# tfp401_board.net
KiCad netlist of a schematic drawn in EAGLE
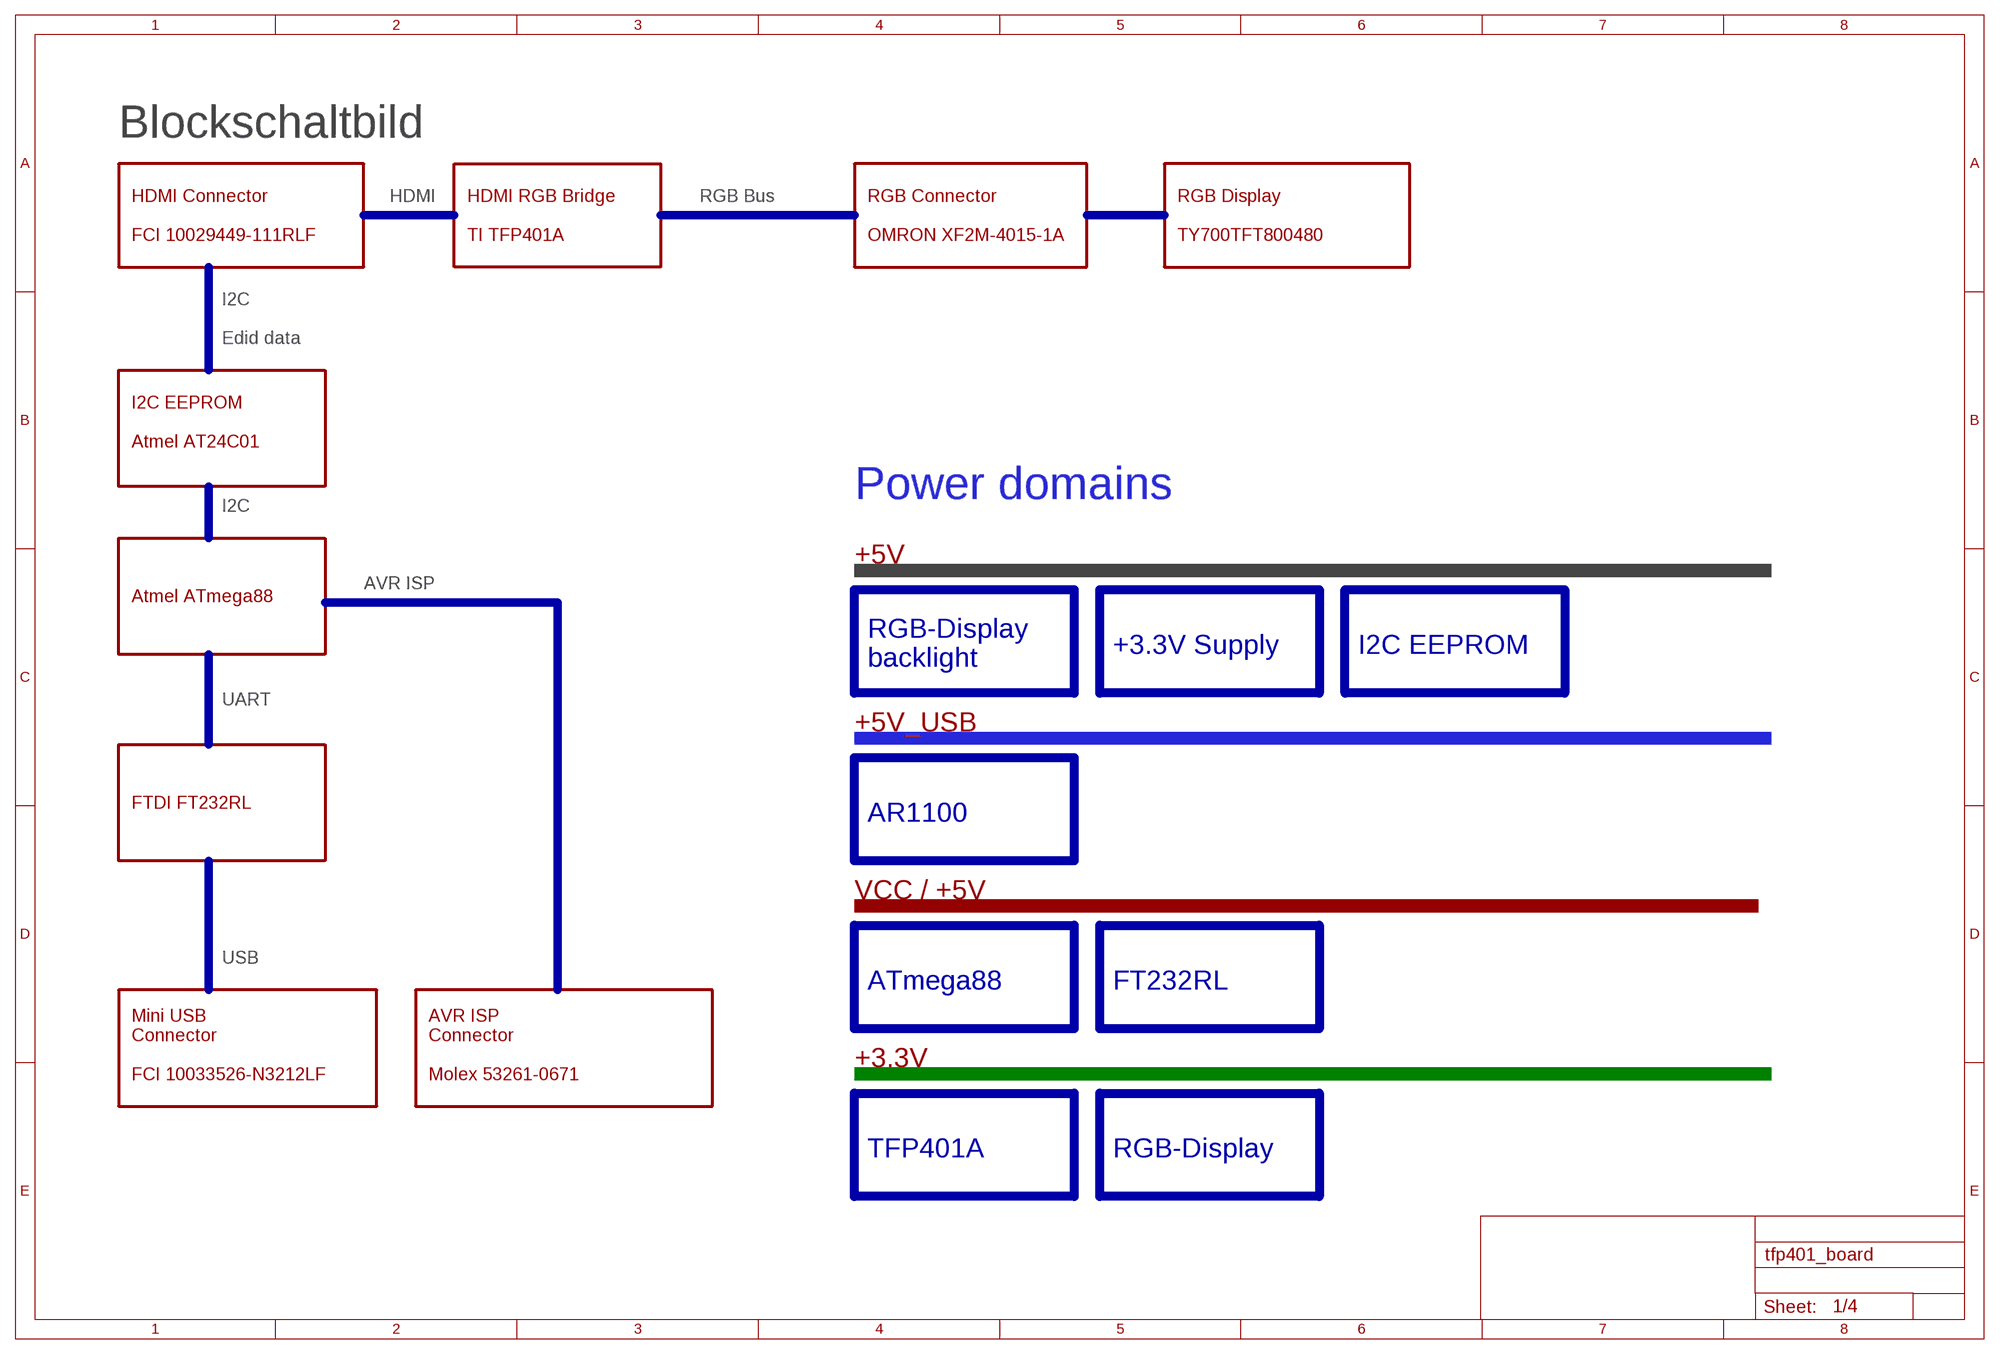
[diagram p0: schematic, sheet 1]
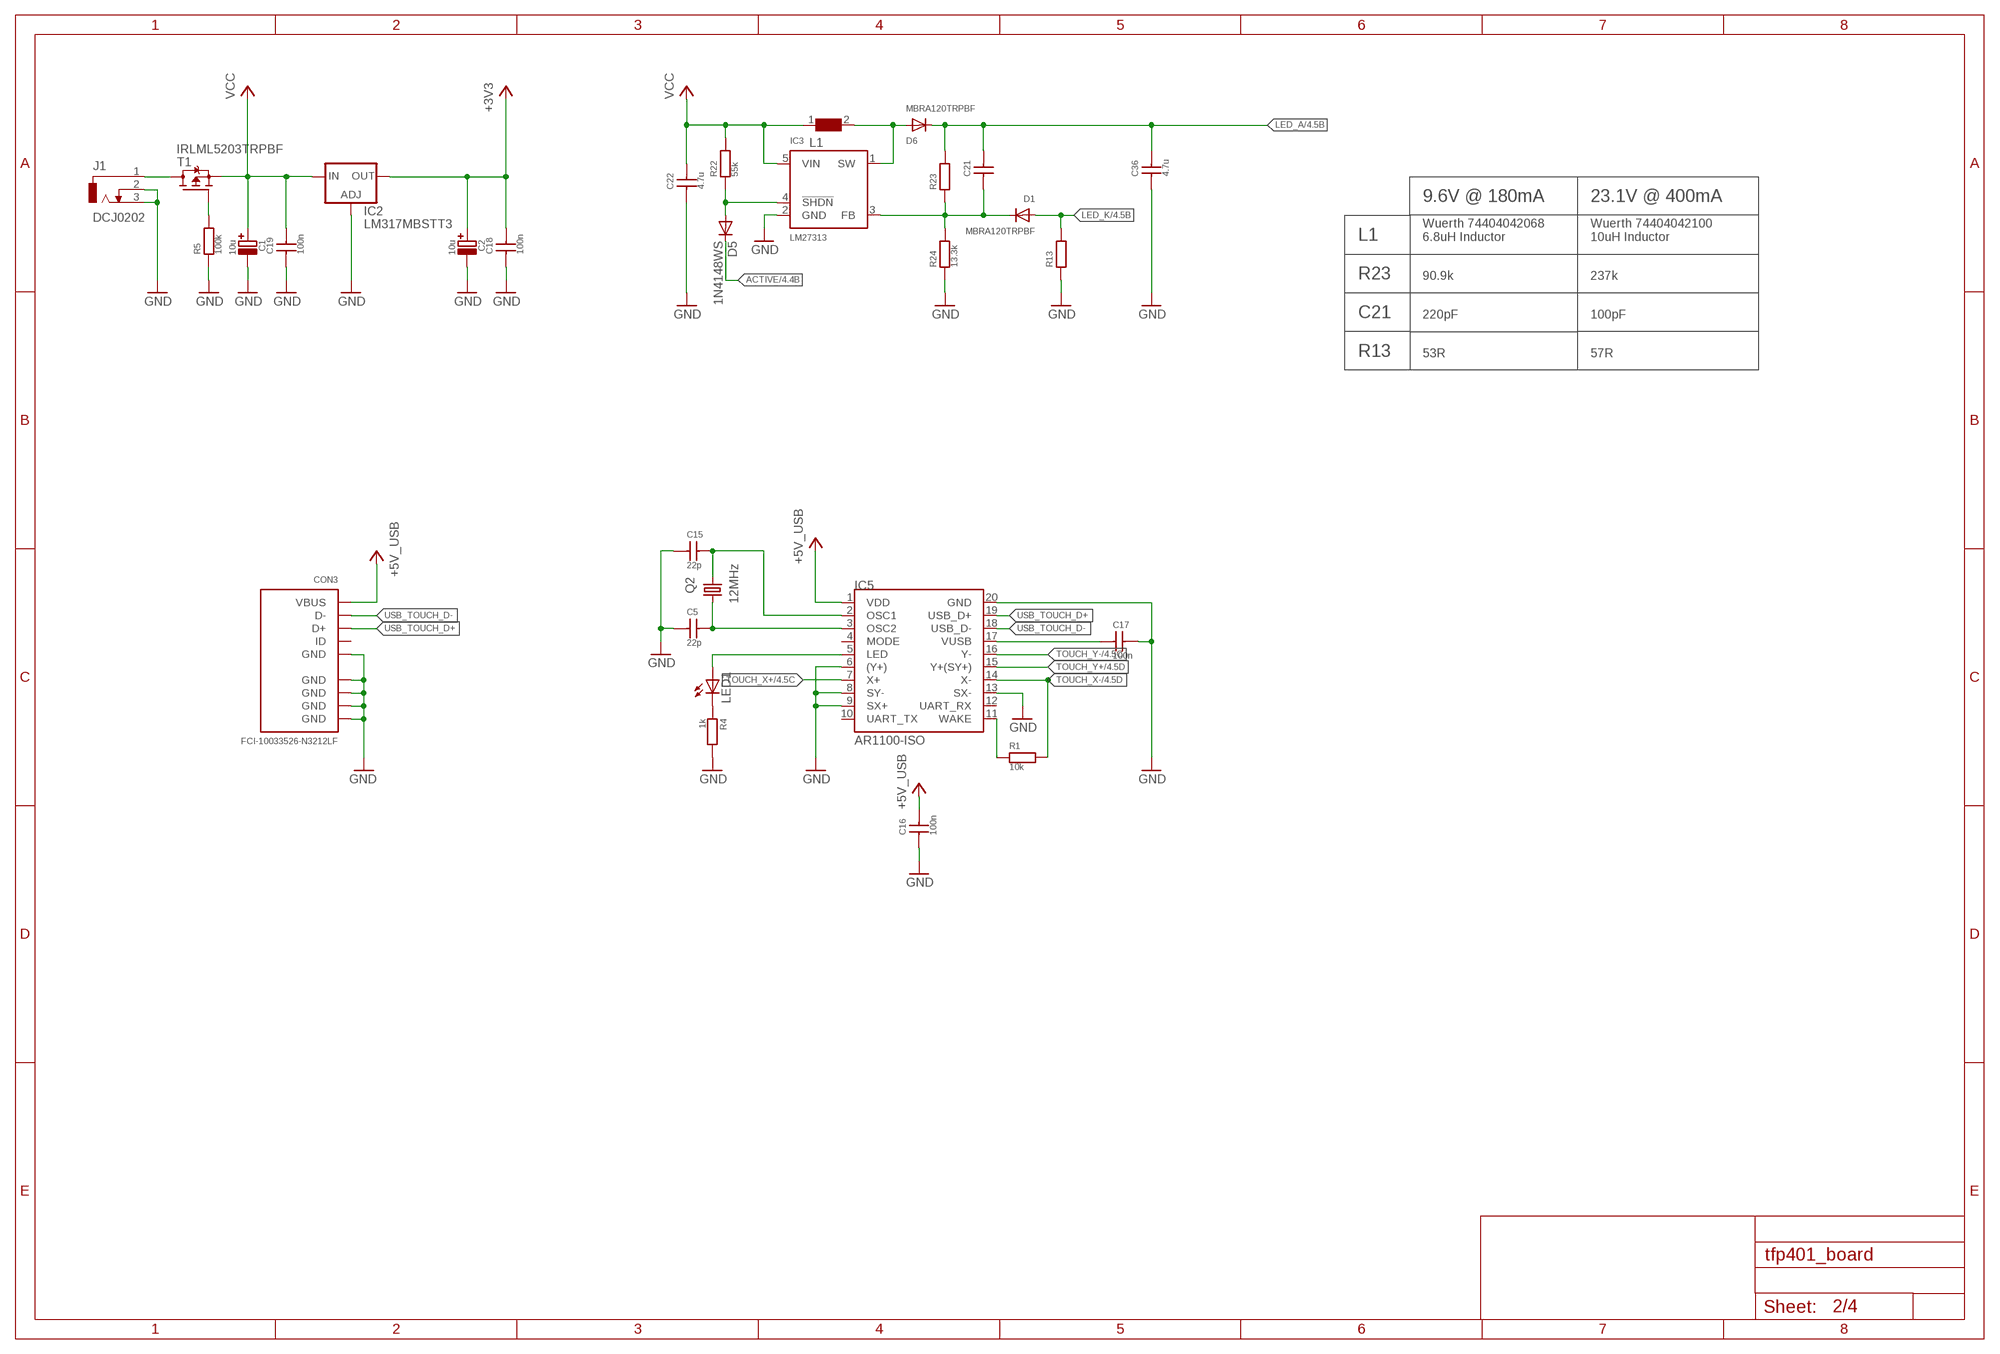
[diagram p1: schematic, sheet 2]
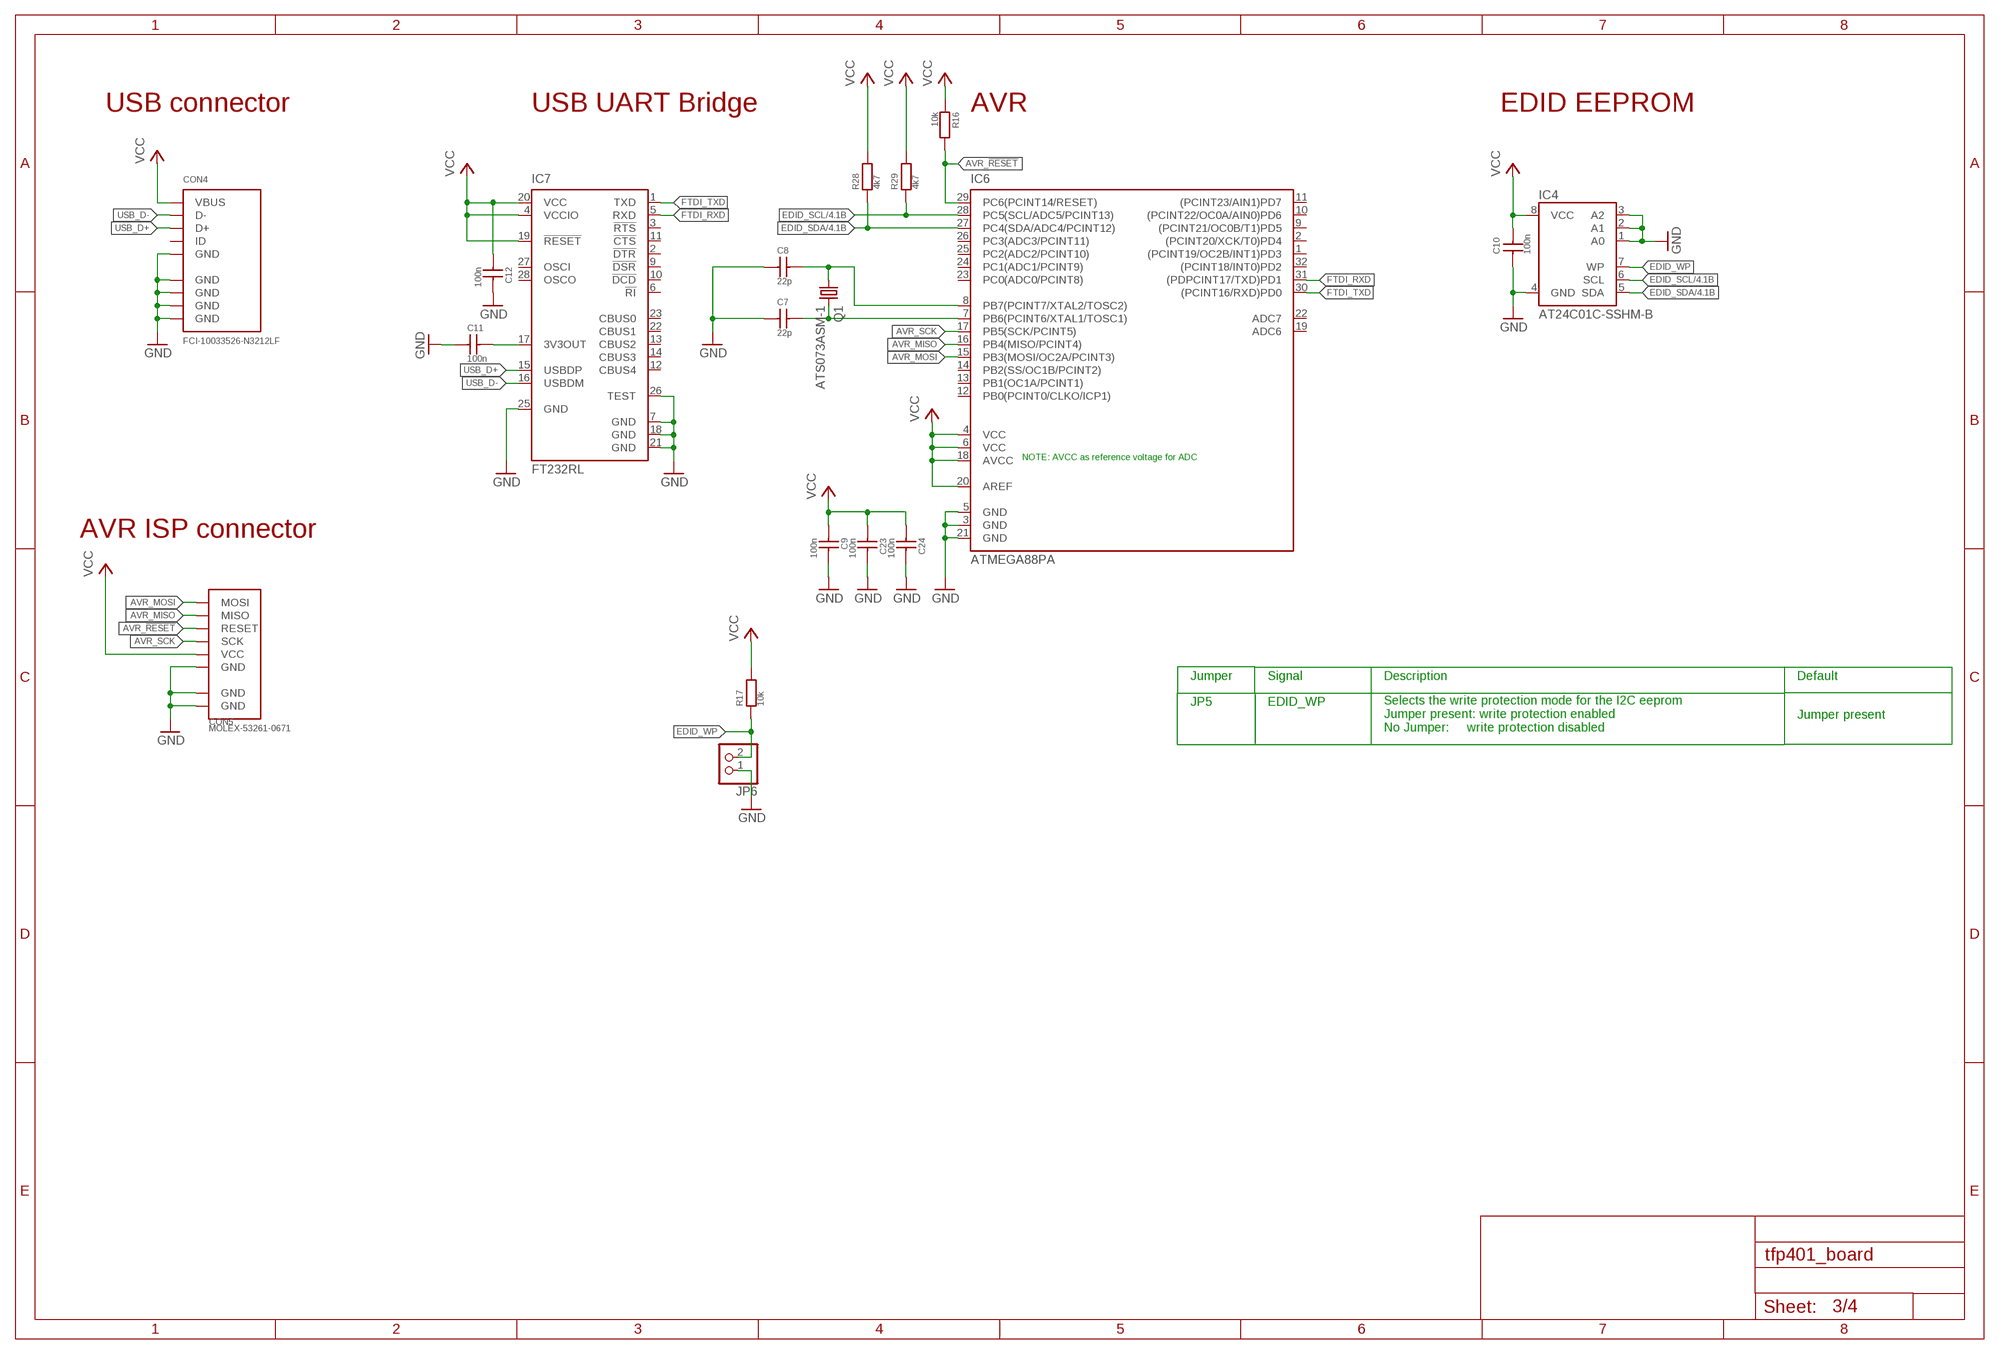
[diagram p2: schematic, sheet 3]
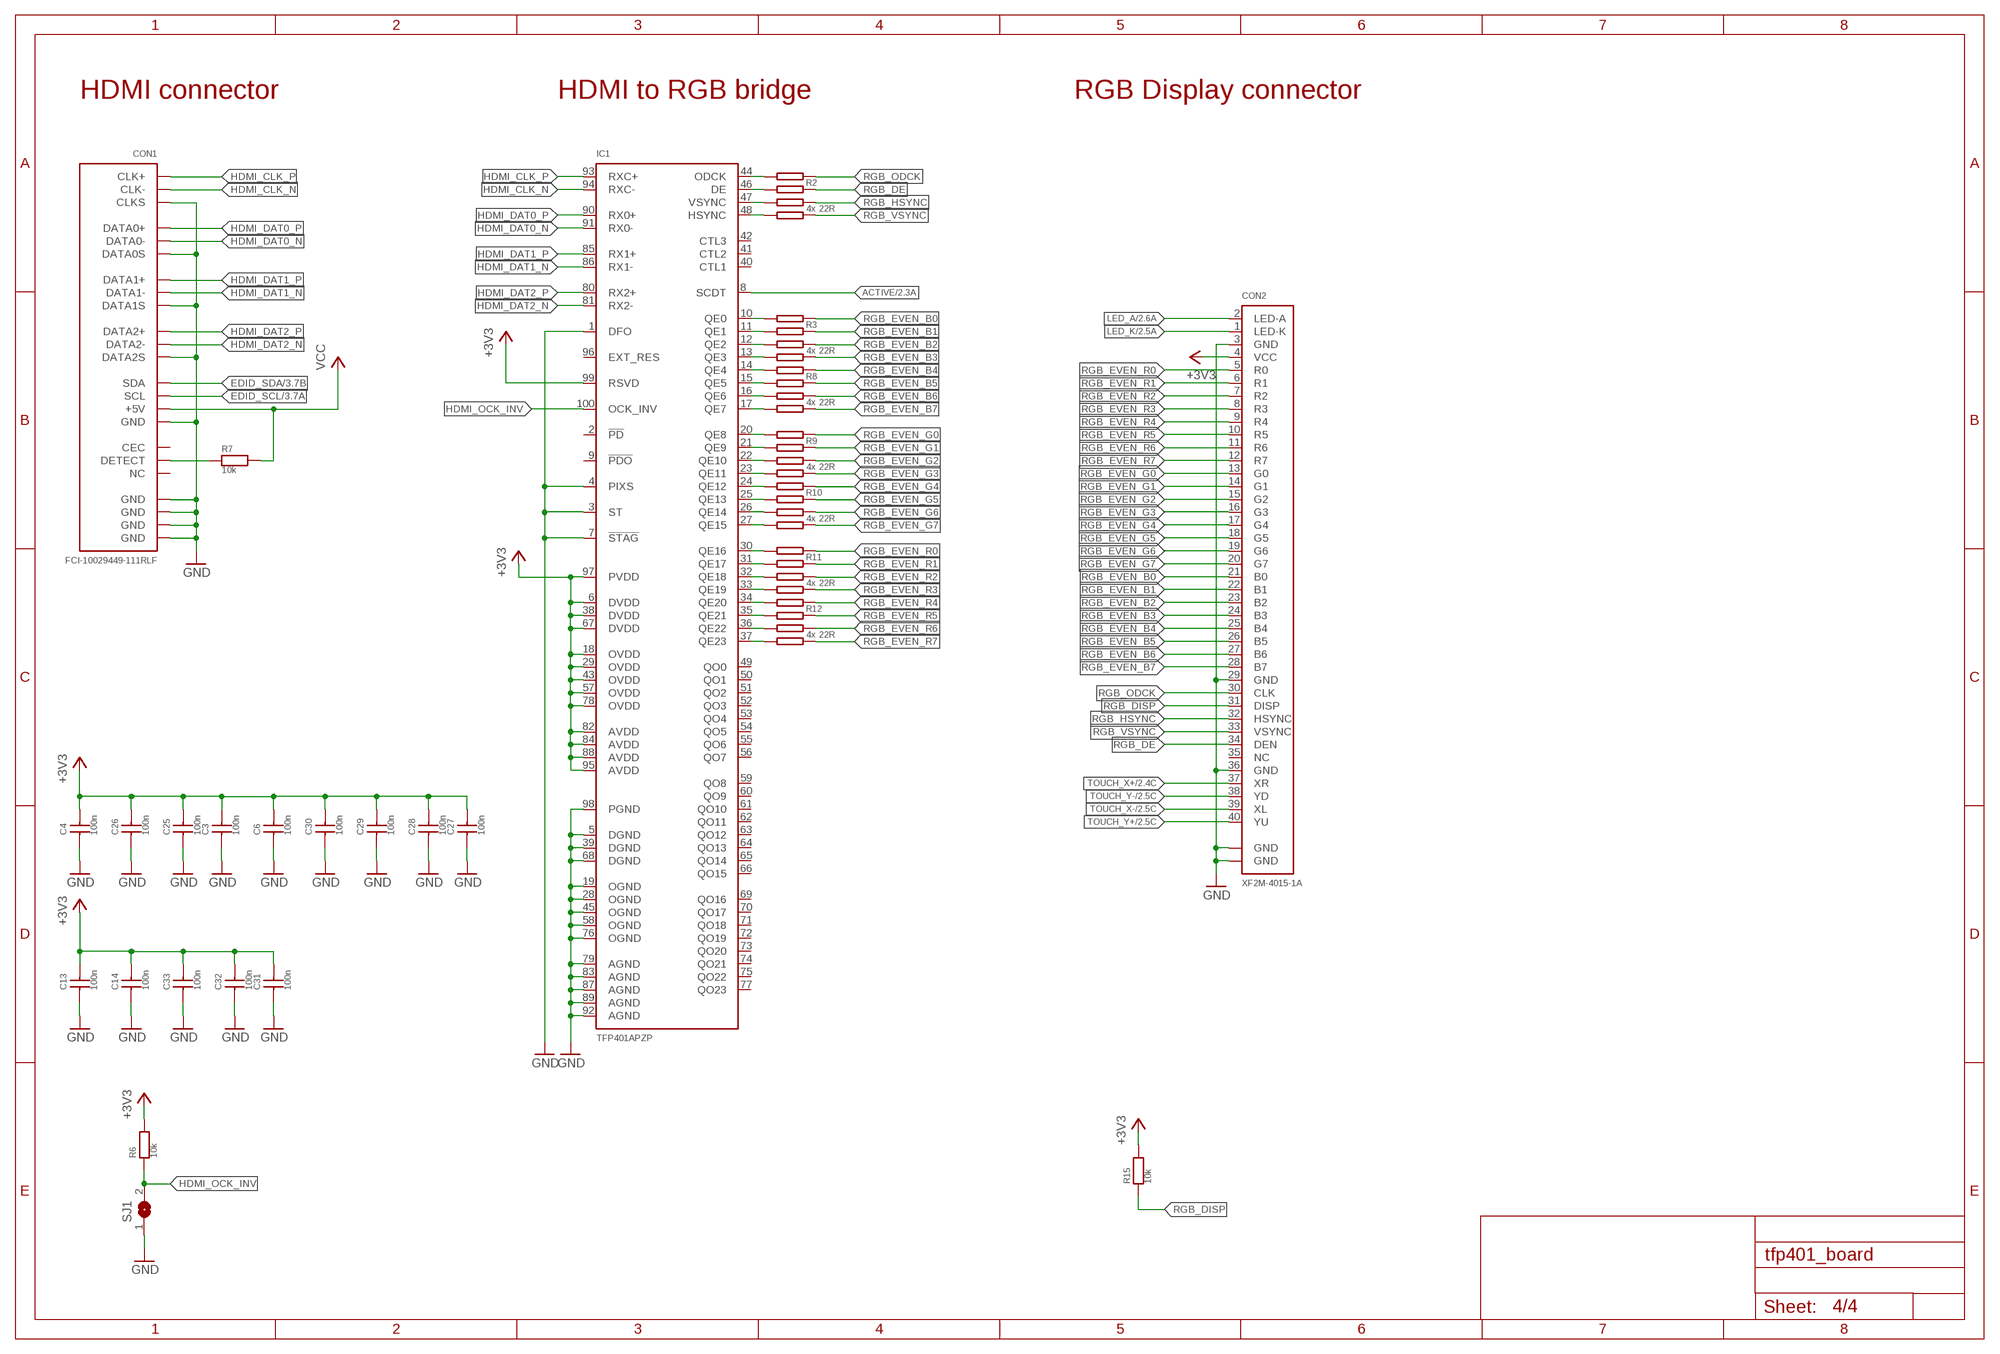
[diagram p3: schematic, sheet 4]

(export (version "E")
  (design (tool "Eeschema 10.0.6"))
  (components
    (comp (ref "U$15")
      (value "FRAME_A3_LANDSCAPE")
      (footprint "eagle-import:FRAME")
      (libsource (lib "eagle-import") (part "FRAME_A3_LANDSCAPE"))
    )
    (comp (ref "C3")
      (value "100n")
      (footprint "eagle-import:C0603")
      (libsource (lib "eagle-import") (part "C_SMD0603"))
    )
    (comp (ref "C4")
      (value "100n")
      (footprint "eagle-import:C0603")
      (libsource (lib "eagle-import") (part "C_SMD0603"))
    )
    (comp (ref "C6")
      (value "100n")
      (footprint "eagle-import:C0603")
      (libsource (lib "eagle-import") (part "C_SMD0603"))
    )
    (comp (ref "C13")
      (value "100n")
      (footprint "eagle-import:C0603")
      (libsource (lib "eagle-import") (part "C_SMD0603"))
    )
    (comp (ref "C14")
      (value "100n")
      (footprint "eagle-import:C0603")
      (libsource (lib "eagle-import") (part "C_SMD0603"))
    )
    (comp (ref "C25")
      (value "100n")
      (footprint "eagle-import:C0603")
      (libsource (lib "eagle-import") (part "C_SMD0603"))
    )
    (comp (ref "C26")
      (value "100n")
      (footprint "eagle-import:C0603")
      (libsource (lib "eagle-import") (part "C_SMD0603"))
    )
    (comp (ref "C27")
      (value "100n")
      (footprint "eagle-import:C0603")
      (libsource (lib "eagle-import") (part "C_SMD0603"))
    )
    (comp (ref "C28")
      (value "100n")
      (footprint "eagle-import:C0603")
      (libsource (lib "eagle-import") (part "C_SMD0603"))
    )
    (comp (ref "C29")
      (value "100n")
      (footprint "eagle-import:C0603")
      (libsource (lib "eagle-import") (part "C_SMD0603"))
    )
    (comp (ref "C30")
      (value "100n")
      (footprint "eagle-import:C0603")
      (libsource (lib "eagle-import") (part "C_SMD0603"))
    )
    (comp (ref "C31")
      (value "100n")
      (footprint "eagle-import:C0603")
      (libsource (lib "eagle-import") (part "C_SMD0603"))
    )
    (comp (ref "C32")
      (value "100n")
      (footprint "eagle-import:C0603")
      (libsource (lib "eagle-import") (part "C_SMD0603"))
    )
    (comp (ref "C33")
      (value "100n")
      (footprint "eagle-import:C0603")
      (libsource (lib "eagle-import") (part "C_SMD0603"))
    )
    (comp (ref "CON1")
      (value "FCI-10029449-111RLF")
      (footprint "eagle-import:FCI-10029449-111RLF")
      (libsource (lib "eagle-import") (part "FCI-10029449-111RLF"))
    )
    (comp (ref "CON2")
      (value "XF2M-4015-1A")
      (footprint "eagle-import:XF2M-4015-1A")
      (libsource (lib "eagle-import") (part "XF2M-4015-1A"))
    )
    (comp (ref "IC1")
      (value "TFP401APZP")
      (footprint "eagle-import:HTQFP-100")
      (libsource (lib "eagle-import") (part "TFP401APZP"))
    )
    (comp (ref "R2")
      (value "22R")
      (footprint "eagle-import:R-ARRAY-4X0603")
      (libsource (lib "eagle-import") (part "CTR-742C083220JP-4X22R-4X0603"))
    )
    (comp (ref "R3")
      (value "22R")
      (footprint "eagle-import:R-ARRAY-4X0603")
      (libsource (lib "eagle-import") (part "CTR-742C083220JP-4X22R-4X0603"))
    )
    (comp (ref "R6")
      (value "10k")
      (footprint "eagle-import:R0603")
      (libsource (lib "eagle-import") (part "R0603"))
    )
    (comp (ref "R7")
      (value "10k")
      (footprint "eagle-import:R0603")
      (libsource (lib "eagle-import") (part "R0603"))
    )
    (comp (ref "R8")
      (value "22R")
      (footprint "eagle-import:R-ARRAY-4X0603")
      (libsource (lib "eagle-import") (part "CTR-742C083220JP-4X22R-4X0603"))
    )
    (comp (ref "R9")
      (value "22R")
      (footprint "eagle-import:R-ARRAY-4X0603")
      (libsource (lib "eagle-import") (part "CTR-742C083220JP-4X22R-4X0603"))
    )
    (comp (ref "R10")
      (value "22R")
      (footprint "eagle-import:R-ARRAY-4X0603")
      (libsource (lib "eagle-import") (part "CTR-742C083220JP-4X22R-4X0603"))
    )
    (comp (ref "R11")
      (value "22R")
      (footprint "eagle-import:R-ARRAY-4X0603")
      (libsource (lib "eagle-import") (part "CTR-742C083220JP-4X22R-4X0603"))
    )
    (comp (ref "R12")
      (value "22R")
      (footprint "eagle-import:R-ARRAY-4X0603")
      (libsource (lib "eagle-import") (part "CTR-742C083220JP-4X22R-4X0603"))
    )
    (comp (ref "R15")
      (value "10k")
      (footprint "eagle-import:R0603")
      (libsource (lib "eagle-import") (part "R0603"))
    )
    (comp (ref "SJ1") (value "SJ") (footprint "eagle-import:SJ") (libsource (lib "eagle-import") (part "SJ")))
    (comp (ref "U$1")
      (value "FRAME_A3_LANDSCAPE")
      (footprint "eagle-import:FRAME")
      (libsource (lib "eagle-import") (part "FRAME_A3_LANDSCAPE"))
    )
    (comp (ref "C1")
      (value "10u")
      (footprint "eagle-import:C_POL_4X4MM")
      (libsource (lib "eagle-import") (part "C_POL4X4MM"))
    )
    (comp (ref "C2")
      (value "10u")
      (footprint "eagle-import:C_POL_4X4MM")
      (libsource (lib "eagle-import") (part "C_POL4X4MM"))
    )
    (comp (ref "C5")
      (value "22p")
      (footprint "eagle-import:C0603")
      (libsource (lib "eagle-import") (part "C_SMD0603"))
    )
    (comp (ref "C15")
      (value "22p")
      (footprint "eagle-import:C0603")
      (libsource (lib "eagle-import") (part "C_SMD0603"))
    )
    (comp (ref "C16")
      (value "100n")
      (footprint "eagle-import:C0603")
      (libsource (lib "eagle-import") (part "C_SMD0603"))
    )
    (comp (ref "C17")
      (value "100n")
      (footprint "eagle-import:C0603")
      (libsource (lib "eagle-import") (part "C_SMD0603"))
    )
    (comp (ref "C18")
      (value "100n")
      (footprint "eagle-import:C0603")
      (libsource (lib "eagle-import") (part "C_SMD0603"))
    )
    (comp (ref "C19")
      (value "100n")
      (footprint "eagle-import:C0603")
      (libsource (lib "eagle-import") (part "C_SMD0603"))
    )
    (comp (ref "C21")
      (value "C_SMD0603")
      (footprint "eagle-import:C0603")
      (libsource (lib "eagle-import") (part "C_SMD0603"))
    )
    (comp (ref "C22")
      (value "4.7u")
      (footprint "eagle-import:C1206")
      (libsource (lib "eagle-import") (part "C_SMD1206"))
    )
    (comp (ref "C36")
      (value "4.7u")
      (footprint "eagle-import:C1206")
      (libsource (lib "eagle-import") (part "C_SMD1206"))
    )
    (comp (ref "CON3")
      (value "FCI-10033526-N3212LF")
      (footprint "eagle-import:FCI-10033526-N3212LF")
      (libsource (lib "eagle-import") (part "FCI-10033526-N3212LF"))
    )
    (comp (ref "D1")
      (value "MBRA120TRPBF")
      (footprint "eagle-import:SMADIODE")
      (libsource (lib "eagle-import") (part "DIODESMA"))
    )
    (comp (ref "D5")
      (value "1N4148WS")
      (footprint "eagle-import:SOD323-W")
      (libsource (lib "eagle-import") (part "DIODE-SOD323-W"))
    )
    (comp (ref "D6")
      (value "MBRA120TRPBF")
      (footprint "eagle-import:SMADIODE")
      (libsource (lib "eagle-import") (part "DIODESMA"))
    )
    (comp (ref "IC2")
      (value "LM317MBSTT3")
      (footprint "eagle-import:SOT223")
      (libsource (lib "eagle-import") (part "LM317?MBSTT3"))
    )
    (comp (ref "IC3")
      (value "LM27313")
      (footprint "eagle-import:SOT23-5")
      (libsource (lib "eagle-import") (part "LM27313"))
    )
    (comp (ref "IC5")
      (value "AR1100-ISO")
      (footprint "eagle-import:SOIC20")
      (libsource (lib "eagle-import") (part "AR1100-ISO"))
    )
    (comp (ref "J1")
      (value "DCJ0202")
      (footprint "eagle-import:DCJ0202")
      (libsource (lib "eagle-import") (part "DCJ0202"))
    )
    (comp (ref "L1")
      (value "WE-LQS_4018")
      (footprint "eagle-import:WE-LQS_4018")
      (libsource (lib "eagle-import") (part "WE-LQS_4018"))
    )
    (comp (ref "LED1")
      (value "LEDCHIP-LED0805")
      (footprint "eagle-import:CHIP-LED0805")
      (libsource (lib "eagle-import") (part "LEDCHIP-LED0805"))
    )
    (comp (ref "Q2")
      (value "12MHz")
      (footprint "eagle-import:HC49_USSM")
      (libsource (lib "eagle-import") (part "ATS073ASM-1"))
    )
    (comp (ref "R1")
      (value "10k")
      (footprint "eagle-import:R0603")
      (libsource (lib "eagle-import") (part "R0603"))
    )
    (comp (ref "R4")
      (value "1k")
      (footprint "eagle-import:R0603")
      (libsource (lib "eagle-import") (part "R0603"))
    )
    (comp (ref "R5")
      (value "100k")
      (footprint "eagle-import:R0603")
      (libsource (lib "eagle-import") (part "R0603"))
    )
    (comp (ref "R13")
      (value "R2512")
      (footprint "eagle-import:R2512")
      (libsource (lib "eagle-import") (part "R2512"))
    )
    (comp (ref "R22")
      (value "55k")
      (footprint "eagle-import:R0603")
      (libsource (lib "eagle-import") (part "R0603"))
    )
    (comp (ref "R23")
      (value "R0603")
      (footprint "eagle-import:R0603")
      (libsource (lib "eagle-import") (part "R0603"))
    )
    (comp (ref "R24")
      (value "13.3k")
      (footprint "eagle-import:R0603")
      (libsource (lib "eagle-import") (part "R0603"))
    )
    (comp (ref "T1")
      (value "IRLML5203TRPBF")
      (footprint "eagle-import:SOT23")
      (libsource (lib "eagle-import") (part "IRLML5203TRPBF"))
    )
    (comp (ref "U$2")
      (value "FRAME_A3_LANDSCAPE")
      (footprint "eagle-import:FRAME")
      (libsource (lib "eagle-import") (part "FRAME_A3_LANDSCAPE"))
    )
    (comp (ref "C7")
      (value "22p")
      (footprint "eagle-import:C0603")
      (libsource (lib "eagle-import") (part "C_SMD0603"))
    )
    (comp (ref "C8")
      (value "22p")
      (footprint "eagle-import:C0603")
      (libsource (lib "eagle-import") (part "C_SMD0603"))
    )
    (comp (ref "C9")
      (value "100n")
      (footprint "eagle-import:C0603")
      (libsource (lib "eagle-import") (part "C_SMD0603"))
    )
    (comp (ref "C10")
      (value "100n")
      (footprint "eagle-import:C0603")
      (libsource (lib "eagle-import") (part "C_SMD0603"))
    )
    (comp (ref "C11")
      (value "100n")
      (footprint "eagle-import:C0603")
      (libsource (lib "eagle-import") (part "C_SMD0603"))
    )
    (comp (ref "C12")
      (value "100n")
      (footprint "eagle-import:C0603")
      (libsource (lib "eagle-import") (part "C_SMD0603"))
    )
    (comp (ref "C23")
      (value "100n")
      (footprint "eagle-import:C0603")
      (libsource (lib "eagle-import") (part "C_SMD0603"))
    )
    (comp (ref "C24")
      (value "100n")
      (footprint "eagle-import:C0603")
      (libsource (lib "eagle-import") (part "C_SMD0603"))
    )
    (comp (ref "CON4")
      (value "FCI-10033526-N3212LF")
      (footprint "eagle-import:FCI-10033526-N3212LF")
      (libsource (lib "eagle-import") (part "FCI-10033526-N3212LF"))
    )
    (comp (ref "CON5")
      (value "MOLEX-53261-0671")
      (footprint "eagle-import:MOLEX-53261-0671")
      (libsource (lib "eagle-import") (part "MOLEX-53261-0671"))
    )
    (comp (ref "IC4")
      (value "AT24C01C-SSHM-B")
      (footprint "eagle-import:SOIC8")
      (libsource (lib "eagle-import") (part "AT24C01C-SSHM-B"))
    )
    (comp (ref "IC6")
      (value "ATMEGA88PA")
      (footprint "eagle-import:TQFP32")
      (libsource (lib "eagle-import") (part "ATMEGA48A-AU"))
    )
    (comp (ref "IC7")
      (value "FT232RL")
      (footprint "eagle-import:SSOP28")
      (libsource (lib "eagle-import") (part "FT232RL"))
    )
    (comp (ref "JP6")
      (value "PINHD-1X02_2.54-SMD-90°")
      (footprint "eagle-import:1X02SMD_90")
      (libsource (lib "eagle-import") (part "PINHD-1X02_2.54-SMD-90°"))
    )
    (comp (ref "Q1")
      (value "ATS073ASM-1")
      (footprint "eagle-import:HC49_USSM")
      (libsource (lib "eagle-import") (part "ATS073ASM-1"))
    )
    (comp (ref "R16")
      (value "10k")
      (footprint "eagle-import:R0603")
      (libsource (lib "eagle-import") (part "R0603"))
    )
    (comp (ref "R17")
      (value "10k")
      (footprint "eagle-import:R0603")
      (libsource (lib "eagle-import") (part "R0603"))
    )
    (comp (ref "R28")
      (value "4k7")
      (footprint "eagle-import:R0603")
      (libsource (lib "eagle-import") (part "R0603"))
    )
    (comp (ref "R29")
      (value "4k7")
      (footprint "eagle-import:R0603")
      (libsource (lib "eagle-import") (part "R0603"))
    )
    (comp (ref "U$4")
      (value "FRAME_A3_LANDSCAPE")
      (footprint "eagle-import:FRAME")
      (libsource (lib "eagle-import") (part "FRAME_A3_LANDSCAPE"))
    )
  )
  (nets
    (net (code "3") (name "+3V3") (class "Default")
      (node (ref "C13") (pin "2") (pinfunction "P$2_2") (pintype "passive"))
      (node (ref "C14") (pin "2") (pinfunction "P$2_2") (pintype "passive"))
      (node (ref "C18") (pin "2") (pinfunction "P$2_2") (pintype "passive"))
      (node (ref "C2") (pin "+") (pinfunction "+_+") (pintype "passive"))
      (node (ref "C25") (pin "2") (pinfunction "P$2_2") (pintype "passive"))
      (node (ref "C26") (pin "2") (pinfunction "P$2_2") (pintype "passive"))
      (node (ref "C27") (pin "2") (pinfunction "P$2_2") (pintype "passive"))
      (node (ref "C28") (pin "2") (pinfunction "P$2_2") (pintype "passive"))
      (node (ref "C29") (pin "2") (pinfunction "P$2_2") (pintype "passive"))
      (node (ref "C3") (pin "2") (pinfunction "P$2_2") (pintype "passive"))
      (node (ref "C30") (pin "2") (pinfunction "P$2_2") (pintype "passive"))
      (node (ref "C31") (pin "2") (pinfunction "P$2_2") (pintype "passive"))
      (node (ref "C32") (pin "2") (pinfunction "P$2_2") (pintype "passive"))
      (node (ref "C33") (pin "2") (pinfunction "P$2_2") (pintype "passive"))
      (node (ref "C4") (pin "2") (pinfunction "P$2_2") (pintype "passive"))
      (node (ref "C6") (pin "2") (pinfunction "P$2_2") (pintype "passive"))
      (node (ref "CON2") (pin "4") (pinfunction "VCC_4") (pintype "bidirectional"))
      (node (ref "IC1") (pin "18") (pinfunction "OVDD_18") (pintype "power_in"))
      (node (ref "IC1") (pin "29") (pinfunction "OVDD_29") (pintype "power_in"))
      (node (ref "IC1") (pin "38") (pinfunction "DVDD_38") (pintype "power_in"))
      (node (ref "IC1") (pin "43") (pinfunction "OVDD_43") (pintype "power_in"))
      (node (ref "IC1") (pin "57") (pinfunction "OVDD_57") (pintype "power_in"))
      (node (ref "IC1") (pin "6") (pinfunction "DVDD_6") (pintype "power_in"))
      (node (ref "IC1") (pin "67") (pinfunction "DVDD_67") (pintype "power_in"))
      (node (ref "IC1") (pin "78") (pinfunction "OVDD_78") (pintype "power_in"))
      (node (ref "IC1") (pin "82") (pinfunction "AVDD_82") (pintype "power_in"))
      (node (ref "IC1") (pin "84") (pinfunction "AVDD_84") (pintype "power_in"))
      (node (ref "IC1") (pin "88") (pinfunction "AVDD_88") (pintype "power_in"))
      (node (ref "IC1") (pin "95") (pinfunction "AVDD_95") (pintype "power_in"))
      (node (ref "IC1") (pin "97") (pinfunction "PVDD_97") (pintype "power_in"))
      (node (ref "IC1") (pin "99") (pinfunction "RSVD_99") (pintype "bidirectional"))
      (node (ref "IC2") (pin "4") (pinfunction "OUT_4") (pintype "passive"))
      (node (ref "R15") (pin "2") (pinfunction "P$2_2") (pintype "passive"))
      (node (ref "R6") (pin "2") (pinfunction "P$2_2") (pintype "passive"))
    )
    (net (code "4") (name "+5V_USB") (class "Default")
      (node (ref "C16") (pin "2") (pinfunction "P$2_2") (pintype "passive"))
      (node (ref "CON3") (pin "1") (pinfunction "VBUS_1") (pintype "bidirectional"))
      (node (ref "IC5") (pin "1") (pinfunction "VDD_1") (pintype "passive"))
    )
    (net (code "7") (name "ACTIVE") (class "Default")
      (node (ref "D5") (pin "C") (pinfunction "C_C") (pintype "passive"))
      (node (ref "IC1") (pin "8") (pinfunction "SCDT_8") (pintype "bidirectional"))
    )
    (net (code "8") (name "AVR_MISO") (class "Default")
      (node (ref "CON5") (pin "2") (pinfunction "MISO_2") (pintype "bidirectional"))
      (node (ref "IC6") (pin "16") (pinfunction "PB4(MISO/PCINT4)_16") (pintype "bidirectional"))
    )
    (net (code "9") (name "AVR_MOSI") (class "Default")
      (node (ref "CON5") (pin "1") (pinfunction "MOSI_1") (pintype "bidirectional"))
      (node (ref "IC6") (pin "15") (pinfunction "PB3(MOSI/OC2A/PCINT3)_15") (pintype "bidirectional"))
    )
    (net (code "10") (name "AVR_SCK") (class "Default")
      (node (ref "CON5") (pin "4") (pinfunction "SCK_4") (pintype "bidirectional"))
      (node (ref "IC6") (pin "17") (pinfunction "PB5(SCK/PCINT5)_17") (pintype "bidirectional"))
    )
    (net (code "11") (name "AVR_~{RESET}") (class "Default")
      (node (ref "CON5") (pin "3") (pinfunction "RESET_3") (pintype "bidirectional"))
      (node (ref "IC6") (pin "29") (pinfunction "PC6(PCINT14/RESET)_29") (pintype "bidirectional"))
      (node (ref "R16") (pin "2") (pinfunction "P$2_2") (pintype "passive"))
    )
    (net (code "12") (name "EDID_SCL") (class "Default")
      (node (ref "CON1") (pin "15") (pinfunction "SCL_15") (pintype "bidirectional"))
      (node (ref "IC4") (pin "6") (pinfunction "SCL_6") (pintype "bidirectional"))
      (node (ref "IC6") (pin "28") (pinfunction "PC5(SCL/ADC5/PCINT13)_28") (pintype "bidirectional"))
      (node (ref "R29") (pin "1") (pinfunction "P$1_1") (pintype "passive"))
    )
    (net (code "13") (name "EDID_SDA") (class "Default")
      (node (ref "CON1") (pin "16") (pinfunction "SDA_16") (pintype "bidirectional"))
      (node (ref "IC4") (pin "5") (pinfunction "SDA_5") (pintype "bidirectional"))
      (node (ref "IC6") (pin "27") (pinfunction "PC4(SDA/ADC4/PCINT12)_27") (pintype "bidirectional"))
      (node (ref "R28") (pin "1") (pinfunction "P$1_1") (pintype "passive"))
    )
    (net (code "14") (name "EDID_WP") (class "Default")
      (node (ref "IC4") (pin "7") (pinfunction "WP_7") (pintype "input"))
      (node (ref "JP6") (pin "2") (pinfunction "2_2") (pintype "passive"))
      (node (ref "R17") (pin "1") (pinfunction "P$1_1") (pintype "passive"))
    )
    (net (code "15") (name "FTDI_RXD") (class "Default")
      (node (ref "IC6") (pin "31") (pinfunction "(PDPCINT17/TXD)PD1_31") (pintype "bidirectional"))
      (node (ref "IC7") (pin "5") (pinfunction "RXD_5") (pintype "input"))
    )
    (net (code "16") (name "FTDI_TXD") (class "Default")
      (node (ref "IC6") (pin "30") (pinfunction "(PCINT16/RXD)PD0_30") (pintype "bidirectional"))
      (node (ref "IC7") (pin "1") (pinfunction "TXD_1") (pintype "output"))
    )
    (net (code "17") (name "GND") (class "Default")
      (node (ref "C1") (pin "-") (pinfunction "-_-") (pintype "passive"))
      (node (ref "C10") (pin "1") (pinfunction "P$1_1") (pintype "passive"))
      (node (ref "C11") (pin "1") (pinfunction "P$1_1") (pintype "passive"))
      (node (ref "C12") (pin "2") (pinfunction "P$2_2") (pintype "passive"))
      (node (ref "C13") (pin "1") (pinfunction "P$1_1") (pintype "passive"))
      (node (ref "C14") (pin "1") (pinfunction "P$1_1") (pintype "passive"))
      (node (ref "C15") (pin "1") (pinfunction "P$1_1") (pintype "passive"))
      (node (ref "C16") (pin "1") (pinfunction "P$1_1") (pintype "passive"))
      (node (ref "C17") (pin "2") (pinfunction "P$2_2") (pintype "passive"))
      (node (ref "C18") (pin "1") (pinfunction "P$1_1") (pintype "passive"))
      (node (ref "C19") (pin "1") (pinfunction "P$1_1") (pintype "passive"))
      (node (ref "C2") (pin "-") (pinfunction "-_-") (pintype "passive"))
      (node (ref "C22") (pin "1") (pinfunction "P$1_1") (pintype "passive"))
      (node (ref "C23") (pin "2") (pinfunction "P$2_2") (pintype "passive"))
      (node (ref "C24") (pin "2") (pinfunction "P$2_2") (pintype "passive"))
      (node (ref "C25") (pin "1") (pinfunction "P$1_1") (pintype "passive"))
      (node (ref "C26") (pin "1") (pinfunction "P$1_1") (pintype "passive"))
      (node (ref "C27") (pin "1") (pinfunction "P$1_1") (pintype "passive"))
      (node (ref "C28") (pin "1") (pinfunction "P$1_1") (pintype "passive"))
      (node (ref "C29") (pin "1") (pinfunction "P$1_1") (pintype "passive"))
      (node (ref "C3") (pin "1") (pinfunction "P$1_1") (pintype "passive"))
      (node (ref "C30") (pin "1") (pinfunction "P$1_1") (pintype "passive"))
      (node (ref "C31") (pin "1") (pinfunction "P$1_1") (pintype "passive"))
      (node (ref "C32") (pin "1") (pinfunction "P$1_1") (pintype "passive"))
      (node (ref "C33") (pin "1") (pinfunction "P$1_1") (pintype "passive"))
      (node (ref "C36") (pin "1") (pinfunction "P$1_1") (pintype "passive"))
      (node (ref "C4") (pin "1") (pinfunction "P$1_1") (pintype "passive"))
      (node (ref "C5") (pin "1") (pinfunction "P$1_1") (pintype "passive"))
      (node (ref "C6") (pin "1") (pinfunction "P$1_1") (pintype "passive"))
      (node (ref "C7") (pin "1") (pinfunction "P$1_1") (pintype "passive"))
      (node (ref "C8") (pin "1") (pinfunction "P$1_1") (pintype "passive"))
      (node (ref "C9") (pin "2") (pinfunction "P$2_2") (pintype "passive"))
      (node (ref "CON1") (pin "11") (pinfunction "CLKS_11") (pintype "bidirectional"))
      (node (ref "CON1") (pin "17") (pinfunction "GND_17") (pintype "bidirectional"))
      (node (ref "CON1") (pin "2") (pinfunction "DATA2S_2") (pintype "bidirectional"))
      (node (ref "CON1") (pin "5") (pinfunction "DATA1S_5") (pintype "bidirectional"))
      (node (ref "CON1") (pin "8") (pinfunction "DATA0S_8") (pintype "bidirectional"))
      (node (ref "CON1") (pin "GND@1") (pinfunction "GND_GND@1") (pintype "power_in"))
      (node (ref "CON1") (pin "GND@2") (pinfunction "GND_GND@2") (pintype "power_in"))
      (node (ref "CON1") (pin "GND@3") (pinfunction "GND_GND@3") (pintype "power_in"))
      (node (ref "CON1") (pin "GND@4") (pinfunction "GND_GND@4") (pintype "power_in"))
      (node (ref "CON2") (pin "29") (pinfunction "GND_29") (pintype "bidirectional"))
      (node (ref "CON2") (pin "3") (pinfunction "GND_3") (pintype "bidirectional"))
      (node (ref "CON2") (pin "36") (pinfunction "GND_36") (pintype "bidirectional"))
      (node (ref "CON2") (pin "GND@1") (pinfunction "GND_GND@1") (pintype "power_in"))
      (node (ref "CON2") (pin "GND@2") (pinfunction "GND_GND@2") (pintype "power_in"))
      (node (ref "CON3") (pin "5") (pinfunction "GND_5") (pintype "bidirectional"))
      (node (ref "CON3") (pin "GND@1") (pinfunction "GND_GND@1") (pintype "power_in"))
      (node (ref "CON3") (pin "GND@2") (pinfunction "GND_GND@2") (pintype "power_in"))
      (node (ref "CON3") (pin "GND@3") (pinfunction "GND_GND@3") (pintype "power_in"))
      (node (ref "CON3") (pin "GND@4") (pinfunction "GND_GND@4") (pintype "power_in"))
      (node (ref "CON4") (pin "5") (pinfunction "GND_5") (pintype "bidirectional"))
      (node (ref "CON4") (pin "GND@1") (pinfunction "GND_GND@1") (pintype "power_in"))
      (node (ref "CON4") (pin "GND@2") (pinfunction "GND_GND@2") (pintype "power_in"))
      (node (ref "CON4") (pin "GND@3") (pinfunction "GND_GND@3") (pintype "power_in"))
      (node (ref "CON4") (pin "GND@4") (pinfunction "GND_GND@4") (pintype "power_in"))
      (node (ref "CON5") (pin "6") (pinfunction "GND_6") (pintype "bidirectional"))
      (node (ref "CON5") (pin "GND@1") (pinfunction "GND_GND@1") (pintype "power_in"))
      (node (ref "CON5") (pin "GND@2") (pinfunction "GND_GND@2") (pintype "power_in"))
      (node (ref "IC1") (pin "1") (pinfunction "DFO_1") (pintype "bidirectional"))
      (node (ref "IC1") (pin "19") (pinfunction "OGND_19") (pintype "power_in"))
      (node (ref "IC1") (pin "28") (pinfunction "OGND_28") (pintype "power_in"))
      (node (ref "IC1") (pin "3") (pinfunction "ST_3") (pintype "bidirectional"))
      (node (ref "IC1") (pin "39") (pinfunction "DGND_39") (pintype "power_in"))
      (node (ref "IC1") (pin "4") (pinfunction "PIXS_4") (pintype "bidirectional"))
      (node (ref "IC1") (pin "45") (pinfunction "OGND_45") (pintype "power_in"))
      (node (ref "IC1") (pin "5") (pinfunction "DGND_5") (pintype "power_in"))
      (node (ref "IC1") (pin "58") (pinfunction "OGND_58") (pintype "power_in"))
      (node (ref "IC1") (pin "68") (pinfunction "DGND_68") (pintype "power_in"))
      (node (ref "IC1") (pin "7") (pinfunction "~{STAG}_7") (pintype "bidirectional"))
      (node (ref "IC1") (pin "76") (pinfunction "OGND_76") (pintype "power_in"))
      (node (ref "IC1") (pin "79") (pinfunction "AGND_79") (pintype "power_in"))
      (node (ref "IC1") (pin "83") (pinfunction "AGND_83") (pintype "power_in"))
      (node (ref "IC1") (pin "87") (pinfunction "AGND_87") (pintype "power_in"))
      (node (ref "IC1") (pin "89") (pinfunction "AGND_89") (pintype "power_in"))
      (node (ref "IC1") (pin "92") (pinfunction "AGND_92") (pintype "power_in"))
      (node (ref "IC1") (pin "98") (pinfunction "PGND_98") (pintype "power_in"))
      (node (ref "IC2") (pin "1") (pinfunction "ADJ_1") (pintype "input"))
      (node (ref "IC3") (pin "2") (pinfunction "GND_2") (pintype "passive"))
      (node (ref "IC4") (pin "1") (pinfunction "A0_1") (pintype "input"))
      (node (ref "IC4") (pin "2") (pinfunction "A1_2") (pintype "input"))
      (node (ref "IC4") (pin "3") (pinfunction "A2_3") (pintype "input"))
      (node (ref "IC4") (pin "4") (pinfunction "GND_4") (pintype "power_in"))
      (node (ref "IC5") (pin "13") (pinfunction "SX-_13") (pintype "passive"))
      (node (ref "IC5") (pin "20") (pinfunction "GND_20") (pintype "passive"))
      (node (ref "IC5") (pin "6") (pinfunction "(Y+)_6") (pintype "passive"))
      (node (ref "IC5") (pin "8") (pinfunction "SY-_8") (pintype "passive"))
      (node (ref "IC5") (pin "9") (pinfunction "SX+_9") (pintype "passive"))
      (node (ref "IC6") (pin "21") (pinfunction "GND_21") (pintype "power_in"))
      (node (ref "IC6") (pin "3") (pinfunction "GND_3") (pintype "power_in"))
      (node (ref "IC6") (pin "5") (pinfunction "GND_5") (pintype "power_in"))
      (node (ref "IC7") (pin "18") (pinfunction "GND_18") (pintype "power_in"))
      (node (ref "IC7") (pin "21") (pinfunction "GND_21") (pintype "power_in"))
      (node (ref "IC7") (pin "25") (pinfunction "GND_25") (pintype "power_in"))
      (node (ref "IC7") (pin "26") (pinfunction "TEST_26") (pintype "input"))
      (node (ref "IC7") (pin "7") (pinfunction "GND_7") (pintype "power_in"))
      (node (ref "J1") (pin "2") (pinfunction "2_2") (pintype "passive"))
      (node (ref "J1") (pin "3") (pinfunction "3_3") (pintype "passive"))
      (node (ref "JP6") (pin "1") (pinfunction "1_1") (pintype "passive"))
      (node (ref "R13") (pin "1") (pinfunction "P$1_1") (pintype "passive"))
      (node (ref "R24") (pin "1") (pinfunction "P$1_1") (pintype "passive"))
      (node (ref "R4") (pin "2") (pinfunction "P$2_2") (pintype "passive"))
      (node (ref "R5") (pin "1") (pinfunction "P$1_1") (pintype "passive"))
      (node (ref "SJ1") (pin "1") (pinfunction "1_1") (pintype "passive"))
    )
    (net (code "18") (name "HDMI_CLK_N") (class "Default")
      (node (ref "CON1") (pin "12") (pinfunction "CLK-_12") (pintype "bidirectional"))
      (node (ref "IC1") (pin "94") (pinfunction "RXC-_94") (pintype "bidirectional"))
    )
    (net (code "19") (name "HDMI_CLK_P") (class "Default")
      (node (ref "CON1") (pin "10") (pinfunction "CLK+_10") (pintype "bidirectional"))
      (node (ref "IC1") (pin "93") (pinfunction "RXC+_93") (pintype "bidirectional"))
    )
    (net (code "20") (name "HDMI_DAT0_N") (class "Default")
      (node (ref "CON1") (pin "9") (pinfunction "DATA0-_9") (pintype "bidirectional"))
      (node (ref "IC1") (pin "91") (pinfunction "RX0-_91") (pintype "bidirectional"))
    )
    (net (code "21") (name "HDMI_DAT0_P") (class "Default")
      (node (ref "CON1") (pin "7") (pinfunction "DATA0+_7") (pintype "bidirectional"))
      (node (ref "IC1") (pin "90") (pinfunction "RX0+_90") (pintype "bidirectional"))
    )
    (net (code "22") (name "HDMI_DAT1_N") (class "Default")
      (node (ref "CON1") (pin "6") (pinfunction "DATA1-_6") (pintype "bidirectional"))
      (node (ref "IC1") (pin "86") (pinfunction "RX1-_86") (pintype "bidirectional"))
    )
    (net (code "23") (name "HDMI_DAT1_P") (class "Default")
      (node (ref "CON1") (pin "4") (pinfunction "DATA1+_4") (pintype "bidirectional"))
      (node (ref "IC1") (pin "85") (pinfunction "RX1+_85") (pintype "bidirectional"))
    )
    (net (code "24") (name "HDMI_DAT2_N") (class "Default")
      (node (ref "CON1") (pin "3") (pinfunction "DATA2-_3") (pintype "bidirectional"))
      (node (ref "IC1") (pin "81") (pinfunction "RX2-_81") (pintype "bidirectional"))
    )
    (net (code "25") (name "HDMI_DAT2_P") (class "Default")
      (node (ref "CON1") (pin "1") (pinfunction "DATA2+_1") (pintype "bidirectional"))
      (node (ref "IC1") (pin "80") (pinfunction "RX2+_80") (pintype "bidirectional"))
    )
    (net (code "26") (name "HDMI_OCK_INV") (class "Default")
      (node (ref "IC1") (pin "100") (pinfunction "OCK_INV_100") (pintype "bidirectional"))
      (node (ref "R6") (pin "1") (pinfunction "P$1_1") (pintype "passive"))
      (node (ref "SJ1") (pin "2") (pinfunction "2_2") (pintype "passive"))
    )
    (net (code "27") (name "LED_A") (class "Default")
      (node (ref "C21") (pin "2") (pinfunction "P$2_2") (pintype "passive"))
      (node (ref "C36") (pin "2") (pinfunction "P$2_2") (pintype "passive"))
      (node (ref "CON2") (pin "2") (pinfunction "LED-A_2") (pintype "bidirectional"))
      (node (ref "D6") (pin "C") (pinfunction "C_C") (pintype "passive"))
      (node (ref "R23") (pin "2") (pinfunction "P$2_2") (pintype "passive"))
    )
    (net (code "28") (name "LED_K") (class "Default")
      (node (ref "CON2") (pin "1") (pinfunction "LED-K_1") (pintype "bidirectional"))
      (node (ref "D1") (pin "A") (pinfunction "A_A") (pintype "passive"))
      (node (ref "R13") (pin "2") (pinfunction "P$2_2") (pintype "passive"))
    )
    (net (code "29") (name "Net-(C5-P$2)") (class "Default")
      (node (ref "C5") (pin "2") (pinfunction "P$2_2") (pintype "passive"))
      (node (ref "IC5") (pin "3") (pinfunction "OSC2_3") (pintype "passive"))
      (node (ref "Q2") (pin "2") (pinfunction "2_2") (pintype "passive"))
    )
    (net (code "30") (name "Net-(C7-P$2)") (class "Default")
      (node (ref "C7") (pin "2") (pinfunction "P$2_2") (pintype "passive"))
      (node (ref "IC6") (pin "7") (pinfunction "PB6(PCINT6/XTAL1/TOSC1)_7") (pintype "bidirectional"))
      (node (ref "Q1") (pin "2") (pinfunction "2_2") (pintype "passive"))
    )
    (net (code "31") (name "Net-(C8-P$2)") (class "Default")
      (node (ref "C8") (pin "2") (pinfunction "P$2_2") (pintype "passive"))
      (node (ref "IC6") (pin "8") (pinfunction "PB7(PCINT7/XTAL2/TOSC2)_8") (pintype "bidirectional"))
      (node (ref "Q1") (pin "1") (pinfunction "1_1") (pintype "passive"))
    )
    (net (code "32") (name "Net-(C11-P$2)") (class "Default")
      (node (ref "C11") (pin "2") (pinfunction "P$2_2") (pintype "passive"))
      (node (ref "IC7") (pin "17") (pinfunction "3V3OUT_17") (pintype "output"))
    )
    (net (code "33") (name "Net-(C15-P$2)") (class "Default")
      (node (ref "C15") (pin "2") (pinfunction "P$2_2") (pintype "passive"))
      (node (ref "IC5") (pin "2") (pinfunction "OSC1_2") (pintype "passive"))
      (node (ref "Q2") (pin "1") (pinfunction "1_1") (pintype "passive"))
    )
    (net (code "34") (name "Net-(C17-P$1)") (class "Default")
      (node (ref "C17") (pin "1") (pinfunction "P$1_1") (pintype "passive"))
      (node (ref "IC5") (pin "17") (pinfunction "VUSB_17") (pintype "passive"))
    )
    (net (code "35") (name "Net-(C21-P$1)") (class "Default")
      (node (ref "C21") (pin "1") (pinfunction "P$1_1") (pintype "passive"))
      (node (ref "D1") (pin "C") (pinfunction "C_C") (pintype "passive"))
      (node (ref "IC3") (pin "3") (pinfunction "FB_3") (pintype "passive"))
      (node (ref "R23") (pin "1") (pinfunction "P$1_1") (pintype "passive"))
      (node (ref "R24") (pin "2") (pinfunction "P$2_2") (pintype "passive"))
    )
    (net (code "36") (name "Net-(CON1-DETECT)") (class "Default")
      (node (ref "CON1") (pin "19") (pinfunction "DETECT_19") (pintype "bidirectional"))
      (node (ref "R7") (pin "1") (pinfunction "P$1_1") (pintype "passive"))
    )
    (net (code "37") (name "Net-(IC1-DE)") (class "Default")
      (node (ref "IC1") (pin "46") (pinfunction "DE_46") (pintype "bidirectional"))
      (node (ref "R2") (pin "3M") (pinfunction "3M_3M") (pintype "bidirectional"))
    )
    (net (code "38") (name "Net-(IC1-HSYNC)") (class "Default")
      (node (ref "IC1") (pin "48") (pinfunction "HSYNC_48") (pintype "bidirectional"))
      (node (ref "R2") (pin "1M") (pinfunction "1M_1M") (pintype "bidirectional"))
    )
    (net (code "39") (name "Net-(IC1-ODCK)") (class "Default")
      (node (ref "IC1") (pin "44") (pinfunction "ODCK_44") (pintype "bidirectional"))
      (node (ref "R2") (pin "4M") (pinfunction "4M_4M") (pintype "bidirectional"))
    )
    (net (code "40") (name "Net-(IC1-QE0)") (class "Default")
      (node (ref "IC1") (pin "10") (pinfunction "QE0_10") (pintype "bidirectional"))
      (node (ref "R3") (pin "4M") (pinfunction "4M_4M") (pintype "bidirectional"))
    )
    (net (code "41") (name "Net-(IC1-QE1)") (class "Default")
      (node (ref "IC1") (pin "11") (pinfunction "QE1_11") (pintype "bidirectional"))
      (node (ref "R3") (pin "3M") (pinfunction "3M_3M") (pintype "bidirectional"))
    )
    (net (code "42") (name "Net-(IC1-QE2)") (class "Default")
      (node (ref "IC1") (pin "12") (pinfunction "QE2_12") (pintype "bidirectional"))
      (node (ref "R3") (pin "2M") (pinfunction "2M_2M") (pintype "bidirectional"))
    )
    (net (code "43") (name "Net-(IC1-QE3)") (class "Default")
      (node (ref "IC1") (pin "13") (pinfunction "QE3_13") (pintype "bidirectional"))
      (node (ref "R3") (pin "1M") (pinfunction "1M_1M") (pintype "bidirectional"))
    )
    (net (code "44") (name "Net-(IC1-QE4)") (class "Default")
      (node (ref "IC1") (pin "14") (pinfunction "QE4_14") (pintype "bidirectional"))
      (node (ref "R8") (pin "4M") (pinfunction "4M_4M") (pintype "bidirectional"))
    )
    (net (code "45") (name "Net-(IC1-QE5)") (class "Default")
      (node (ref "IC1") (pin "15") (pinfunction "QE5_15") (pintype "bidirectional"))
      (node (ref "R8") (pin "3M") (pinfunction "3M_3M") (pintype "bidirectional"))
    )
    (net (code "46") (name "Net-(IC1-QE6)") (class "Default")
      (node (ref "IC1") (pin "16") (pinfunction "QE6_16") (pintype "bidirectional"))
      (node (ref "R8") (pin "2M") (pinfunction "2M_2M") (pintype "bidirectional"))
    )
    (net (code "47") (name "Net-(IC1-QE7)") (class "Default")
      (node (ref "IC1") (pin "17") (pinfunction "QE7_17") (pintype "bidirectional"))
      (node (ref "R8") (pin "1M") (pinfunction "1M_1M") (pintype "bidirectional"))
    )
    (net (code "48") (name "Net-(IC1-QE8)") (class "Default")
      (node (ref "IC1") (pin "20") (pinfunction "QE8_20") (pintype "bidirectional"))
      (node (ref "R9") (pin "4M") (pinfunction "4M_4M") (pintype "bidirectional"))
    )
    (net (code "49") (name "Net-(IC1-QE9)") (class "Default")
      (node (ref "IC1") (pin "21") (pinfunction "QE9_21") (pintype "bidirectional"))
      (node (ref "R9") (pin "3M") (pinfunction "3M_3M") (pintype "bidirectional"))
    )
    (net (code "50") (name "Net-(IC1-QE10)") (class "Default")
      (node (ref "IC1") (pin "22") (pinfunction "QE10_22") (pintype "bidirectional"))
      (node (ref "R9") (pin "2M") (pinfunction "2M_2M") (pintype "bidirectional"))
    )
    (net (code "51") (name "Net-(IC1-QE11)") (class "Default")
      (node (ref "IC1") (pin "23") (pinfunction "QE11_23") (pintype "bidirectional"))
      (node (ref "R9") (pin "1M") (pinfunction "1M_1M") (pintype "bidirectional"))
    )
    (net (code "52") (name "Net-(IC1-QE12)") (class "Default")
      (node (ref "IC1") (pin "24") (pinfunction "QE12_24") (pintype "bidirectional"))
      (node (ref "R10") (pin "4M") (pinfunction "4M_4M") (pintype "bidirectional"))
    )
    (net (code "53") (name "Net-(IC1-QE13)") (class "Default")
      (node (ref "IC1") (pin "25") (pinfunction "QE13_25") (pintype "bidirectional"))
      (node (ref "R10") (pin "3M") (pinfunction "3M_3M") (pintype "bidirectional"))
    )
    (net (code "54") (name "Net-(IC1-QE14)") (class "Default")
      (node (ref "IC1") (pin "26") (pinfunction "QE14_26") (pintype "bidirectional"))
      (node (ref "R10") (pin "2M") (pinfunction "2M_2M") (pintype "bidirectional"))
    )
    (net (code "55") (name "Net-(IC1-QE15)") (class "Default")
      (node (ref "IC1") (pin "27") (pinfunction "QE15_27") (pintype "bidirectional"))
      (node (ref "R10") (pin "1M") (pinfunction "1M_1M") (pintype "bidirectional"))
    )
    (net (code "56") (name "Net-(IC1-QE16)") (class "Default")
      (node (ref "IC1") (pin "30") (pinfunction "QE16_30") (pintype "bidirectional"))
      (node (ref "R11") (pin "4M") (pinfunction "4M_4M") (pintype "bidirectional"))
    )
    (net (code "57") (name "Net-(IC1-QE17)") (class "Default")
      (node (ref "IC1") (pin "31") (pinfunction "QE17_31") (pintype "bidirectional"))
      (node (ref "R11") (pin "3M") (pinfunction "3M_3M") (pintype "bidirectional"))
    )
    (net (code "58") (name "Net-(IC1-QE18)") (class "Default")
      (node (ref "IC1") (pin "32") (pinfunction "QE18_32") (pintype "bidirectional"))
      (node (ref "R11") (pin "2M") (pinfunction "2M_2M") (pintype "bidirectional"))
    )
    (net (code "59") (name "Net-(IC1-QE19)") (class "Default")
      (node (ref "IC1") (pin "33") (pinfunction "QE19_33") (pintype "bidirectional"))
      (node (ref "R11") (pin "1M") (pinfunction "1M_1M") (pintype "bidirectional"))
    )
    (net (code "60") (name "Net-(IC1-QE20)") (class "Default")
      (node (ref "IC1") (pin "34") (pinfunction "QE20_34") (pintype "bidirectional"))
      (node (ref "R12") (pin "4M") (pinfunction "4M_4M") (pintype "bidirectional"))
    )
    (net (code "61") (name "Net-(IC1-QE21)") (class "Default")
      (node (ref "IC1") (pin "35") (pinfunction "QE21_35") (pintype "bidirectional"))
      (node (ref "R12") (pin "3M") (pinfunction "3M_3M") (pintype "bidirectional"))
    )
    (net (code "62") (name "Net-(IC1-QE22)") (class "Default")
      (node (ref "IC1") (pin "36") (pinfunction "QE22_36") (pintype "bidirectional"))
      (node (ref "R12") (pin "2M") (pinfunction "2M_2M") (pintype "bidirectional"))
    )
    (net (code "63") (name "Net-(IC1-QE23)") (class "Default")
      (node (ref "IC1") (pin "37") (pinfunction "QE23_37") (pintype "bidirectional"))
      (node (ref "R12") (pin "1M") (pinfunction "1M_1M") (pintype "bidirectional"))
    )
    (net (code "64") (name "Net-(IC1-VSYNC)") (class "Default")
      (node (ref "IC1") (pin "47") (pinfunction "VSYNC_47") (pintype "bidirectional"))
      (node (ref "R2") (pin "2M") (pinfunction "2M_2M") (pintype "bidirectional"))
    )
    (net (code "65") (name "Net-(IC3-SW)") (class "Default")
      (node (ref "D6") (pin "A") (pinfunction "A_A") (pintype "passive"))
      (node (ref "IC3") (pin "1") (pinfunction "SW_1") (pintype "passive"))
      (node (ref "L1") (pin "2") (pinfunction "2_2") (pintype "passive"))
    )
    (net (code "66") (name "Net-(IC3-~{SHDN})") (class "Default")
      (node (ref "D5") (pin "A") (pinfunction "A_A") (pintype "passive"))
      (node (ref "IC3") (pin "4") (pinfunction "~{SHDN}_4") (pintype "passive"))
      (node (ref "R22") (pin "1") (pinfunction "P$1_1") (pintype "passive"))
    )
    (net (code "67") (name "Net-(IC5-LED)") (class "Default")
      (node (ref "IC5") (pin "5") (pinfunction "LED_5") (pintype "passive"))
      (node (ref "LED1") (pin "A") (pinfunction "A_A") (pintype "passive"))
    )
    (net (code "68") (name "Net-(IC5-WAKE)") (class "Default")
      (node (ref "IC5") (pin "11") (pinfunction "WAKE_11") (pintype "passive"))
      (node (ref "R1") (pin "1") (pinfunction "P$1_1") (pintype "passive"))
    )
    (net (code "69") (name "Net-(R4-P$1)") (class "Default")
      (node (ref "LED1") (pin "C") (pinfunction "C_C") (pintype "passive"))
      (node (ref "R4") (pin "1") (pinfunction "P$1_1") (pintype "passive"))
    )
    (net (code "70") (name "Net-(R5-P$2)") (class "Default")
      (node (ref "R5") (pin "2") (pinfunction "P$2_2") (pintype "passive"))
      (node (ref "T1") (pin "1") (pinfunction "G_1") (pintype "passive"))
    )
    (net (code "71") (name "Net-(T1-D)") (class "Default")
      (node (ref "J1") (pin "1") (pinfunction "1_1") (pintype "passive"))
      (node (ref "T1") (pin "3") (pinfunction "D_3") (pintype "passive"))
    )
    (net (code "72") (name "RGB_DE") (class "Default")
      (node (ref "CON2") (pin "34") (pinfunction "DEN_34") (pintype "bidirectional"))
      (node (ref "R2") (pin "3P") (pinfunction "3P_3P") (pintype "bidirectional"))
    )
    (net (code "73") (name "RGB_DISP") (class "Default")
      (node (ref "CON2") (pin "31") (pinfunction "DISP_31") (pintype "bidirectional"))
      (node (ref "R15") (pin "1") (pinfunction "P$1_1") (pintype "passive"))
    )
    (net (code "74") (name "RGB_EVEN_B0") (class "Default")
      (node (ref "CON2") (pin "21") (pinfunction "B0_21") (pintype "bidirectional"))
      (node (ref "R3") (pin "4P") (pinfunction "4P_4P") (pintype "bidirectional"))
    )
    (net (code "75") (name "RGB_EVEN_B1") (class "Default")
      (node (ref "CON2") (pin "22") (pinfunction "B1_22") (pintype "bidirectional"))
      (node (ref "R3") (pin "3P") (pinfunction "3P_3P") (pintype "bidirectional"))
    )
    (net (code "76") (name "RGB_EVEN_B2") (class "Default")
      (node (ref "CON2") (pin "23") (pinfunction "B2_23") (pintype "bidirectional"))
      (node (ref "R3") (pin "2P") (pinfunction "2P_2P") (pintype "bidirectional"))
    )
    (net (code "77") (name "RGB_EVEN_B3") (class "Default")
      (node (ref "CON2") (pin "24") (pinfunction "B3_24") (pintype "bidirectional"))
      (node (ref "R3") (pin "1P") (pinfunction "1P_1P") (pintype "bidirectional"))
    )
    (net (code "78") (name "RGB_EVEN_B4") (class "Default")
      (node (ref "CON2") (pin "25") (pinfunction "B4_25") (pintype "bidirectional"))
      (node (ref "R8") (pin "4P") (pinfunction "4P_4P") (pintype "bidirectional"))
    )
    (net (code "79") (name "RGB_EVEN_B5") (class "Default")
      (node (ref "CON2") (pin "26") (pinfunction "B5_26") (pintype "bidirectional"))
      (node (ref "R8") (pin "3P") (pinfunction "3P_3P") (pintype "bidirectional"))
    )
    (net (code "80") (name "RGB_EVEN_B6") (class "Default")
      (node (ref "CON2") (pin "27") (pinfunction "B6_27") (pintype "bidirectional"))
      (node (ref "R8") (pin "2P") (pinfunction "2P_2P") (pintype "bidirectional"))
    )
    (net (code "81") (name "RGB_EVEN_B7") (class "Default")
      (node (ref "CON2") (pin "28") (pinfunction "B7_28") (pintype "bidirectional"))
      (node (ref "R8") (pin "1P") (pinfunction "1P_1P") (pintype "bidirectional"))
    )
    (net (code "82") (name "RGB_EVEN_G0") (class "Default")
      (node (ref "CON2") (pin "13") (pinfunction "G0_13") (pintype "bidirectional"))
      (node (ref "R9") (pin "4P") (pinfunction "4P_4P") (pintype "bidirectional"))
    )
    (net (code "83") (name "RGB_EVEN_G1") (class "Default")
      (node (ref "CON2") (pin "14") (pinfunction "G1_14") (pintype "bidirectional"))
      (node (ref "R9") (pin "3P") (pinfunction "3P_3P") (pintype "bidirectional"))
    )
    (net (code "84") (name "RGB_EVEN_G2") (class "Default")
      (node (ref "CON2") (pin "15") (pinfunction "G2_15") (pintype "bidirectional"))
      (node (ref "R9") (pin "2P") (pinfunction "2P_2P") (pintype "bidirectional"))
    )
    (net (code "85") (name "RGB_EVEN_G3") (class "Default")
      (node (ref "CON2") (pin "16") (pinfunction "G3_16") (pintype "bidirectional"))
      (node (ref "R9") (pin "1P") (pinfunction "1P_1P") (pintype "bidirectional"))
    )
    (net (code "86") (name "RGB_EVEN_G4") (class "Default")
      (node (ref "CON2") (pin "17") (pinfunction "G4_17") (pintype "bidirectional"))
      (node (ref "R10") (pin "4P") (pinfunction "4P_4P") (pintype "bidirectional"))
    )
    (net (code "87") (name "RGB_EVEN_G5") (class "Default")
      (node (ref "CON2") (pin "18") (pinfunction "G5_18") (pintype "bidirectional"))
      (node (ref "R10") (pin "3P") (pinfunction "3P_3P") (pintype "bidirectional"))
    )
    (net (code "88") (name "RGB_EVEN_G6") (class "Default")
      (node (ref "CON2") (pin "19") (pinfunction "G6_19") (pintype "bidirectional"))
      (node (ref "R10") (pin "2P") (pinfunction "2P_2P") (pintype "bidirectional"))
    )
    (net (code "89") (name "RGB_EVEN_G7") (class "Default")
      (node (ref "CON2") (pin "20") (pinfunction "G7_20") (pintype "bidirectional"))
      (node (ref "R10") (pin "1P") (pinfunction "1P_1P") (pintype "bidirectional"))
    )
    (net (code "90") (name "RGB_EVEN_R0") (class "Default")
      (node (ref "CON2") (pin "5") (pinfunction "R0_5") (pintype "bidirectional"))
      (node (ref "R11") (pin "4P") (pinfunction "4P_4P") (pintype "bidirectional"))
    )
    (net (code "91") (name "RGB_EVEN_R1") (class "Default")
      (node (ref "CON2") (pin "6") (pinfunction "R1_6") (pintype "bidirectional"))
      (node (ref "R11") (pin "3P") (pinfunction "3P_3P") (pintype "bidirectional"))
    )
    (net (code "92") (name "RGB_EVEN_R2") (class "Default")
      (node (ref "CON2") (pin "7") (pinfunction "R2_7") (pintype "bidirectional"))
      (node (ref "R11") (pin "2P") (pinfunction "2P_2P") (pintype "bidirectional"))
    )
    (net (code "93") (name "RGB_EVEN_R3") (class "Default")
      (node (ref "CON2") (pin "8") (pinfunction "R3_8") (pintype "bidirectional"))
      (node (ref "R11") (pin "1P") (pinfunction "1P_1P") (pintype "bidirectional"))
    )
    (net (code "94") (name "RGB_EVEN_R4") (class "Default")
      (node (ref "CON2") (pin "9") (pinfunction "R4_9") (pintype "bidirectional"))
      (node (ref "R12") (pin "4P") (pinfunction "4P_4P") (pintype "bidirectional"))
    )
    (net (code "95") (name "RGB_EVEN_R5") (class "Default")
      (node (ref "CON2") (pin "10") (pinfunction "R5_10") (pintype "bidirectional"))
      (node (ref "R12") (pin "3P") (pinfunction "3P_3P") (pintype "bidirectional"))
    )
    (net (code "96") (name "RGB_EVEN_R6") (class "Default")
      (node (ref "CON2") (pin "11") (pinfunction "R6_11") (pintype "bidirectional"))
      (node (ref "R12") (pin "2P") (pinfunction "2P_2P") (pintype "bidirectional"))
    )
    (net (code "97") (name "RGB_EVEN_R7") (class "Default")
      (node (ref "CON2") (pin "12") (pinfunction "R7_12") (pintype "bidirectional"))
      (node (ref "R12") (pin "1P") (pinfunction "1P_1P") (pintype "bidirectional"))
    )
    (net (code "98") (name "RGB_HSYNC") (class "Default")
      (node (ref "CON2") (pin "32") (pinfunction "HSYNC_32") (pintype "bidirectional"))
      (node (ref "R2") (pin "2P") (pinfunction "2P_2P") (pintype "bidirectional"))
    )
    (net (code "99") (name "RGB_ODCK") (class "Default")
      (node (ref "CON2") (pin "30") (pinfunction "CLK_30") (pintype "bidirectional"))
      (node (ref "R2") (pin "4P") (pinfunction "4P_4P") (pintype "bidirectional"))
    )
    (net (code "100") (name "RGB_VSYNC") (class "Default")
      (node (ref "CON2") (pin "33") (pinfunction "VSYNC_33") (pintype "bidirectional"))
      (node (ref "R2") (pin "1P") (pinfunction "1P_1P") (pintype "bidirectional"))
    )
    (net (code "101") (name "TOUCH_X+") (class "Default")
      (node (ref "CON2") (pin "37") (pinfunction "XR_37") (pintype "bidirectional"))
      (node (ref "IC5") (pin "7") (pinfunction "X+_7") (pintype "passive"))
    )
    (net (code "102") (name "TOUCH_X-") (class "Default")
      (node (ref "CON2") (pin "39") (pinfunction "XL_39") (pintype "bidirectional"))
      (node (ref "IC5") (pin "14") (pinfunction "X-_14") (pintype "passive"))
      (node (ref "R1") (pin "2") (pinfunction "P$2_2") (pintype "passive"))
    )
    (net (code "103") (name "TOUCH_Y+") (class "Default")
      (node (ref "CON2") (pin "40") (pinfunction "YU_40") (pintype "bidirectional"))
      (node (ref "IC5") (pin "15") (pinfunction "Y+(SY+)_15") (pintype "passive"))
    )
    (net (code "104") (name "TOUCH_Y-") (class "Default")
      (node (ref "CON2") (pin "38") (pinfunction "YD_38") (pintype "bidirectional"))
      (node (ref "IC5") (pin "16") (pinfunction "Y-_16") (pintype "passive"))
    )
    (net (code "105") (name "USB_D+") (class "Default")
      (node (ref "CON4") (pin "3") (pinfunction "D+_3") (pintype "bidirectional"))
      (node (ref "IC7") (pin "15") (pinfunction "USBDP_15") (pintype "bidirectional"))
    )
    (net (code "106") (name "USB_D-") (class "Default")
      (node (ref "CON4") (pin "2") (pinfunction "D-_2") (pintype "bidirectional"))
      (node (ref "IC7") (pin "16") (pinfunction "USBDM_16") (pintype "bidirectional"))
    )
    (net (code "107") (name "USB_TOUCH_D+") (class "Default")
      (node (ref "CON3") (pin "3") (pinfunction "D+_3") (pintype "bidirectional"))
      (node (ref "IC5") (pin "19") (pinfunction "USB_D+_19") (pintype "passive"))
    )
    (net (code "108") (name "USB_TOUCH_D-") (class "Default")
      (node (ref "CON3") (pin "2") (pinfunction "D-_2") (pintype "bidirectional"))
      (node (ref "IC5") (pin "18") (pinfunction "USB_D-_18") (pintype "passive"))
    )
    (net (code "109") (name "VCC") (class "Default")
      (node (ref "C1") (pin "+") (pinfunction "+_+") (pintype "passive"))
      (node (ref "C10") (pin "2") (pinfunction "P$2_2") (pintype "passive"))
      (node (ref "C12") (pin "1") (pinfunction "P$1_1") (pintype "passive"))
      (node (ref "C19") (pin "2") (pinfunction "P$2_2") (pintype "passive"))
      (node (ref "C22") (pin "2") (pinfunction "P$2_2") (pintype "passive"))
      (node (ref "C23") (pin "1") (pinfunction "P$1_1") (pintype "passive"))
      (node (ref "C24") (pin "1") (pinfunction "P$1_1") (pintype "passive"))
      (node (ref "C9") (pin "1") (pinfunction "P$1_1") (pintype "passive"))
      (node (ref "CON1") (pin "18") (pinfunction "+5V_18") (pintype "bidirectional"))
      (node (ref "CON4") (pin "1") (pinfunction "VBUS_1") (pintype "bidirectional"))
      (node (ref "CON5") (pin "5") (pinfunction "VCC_5") (pintype "bidirectional"))
      (node (ref "IC2") (pin "3") (pinfunction "IN_3") (pintype "input"))
      (node (ref "IC3") (pin "5") (pinfunction "VIN_5") (pintype "passive"))
      (node (ref "IC4") (pin "8") (pinfunction "VCC_8") (pintype "power_in"))
      (node (ref "IC6") (pin "18") (pinfunction "AVCC_18") (pintype "power_in"))
      (node (ref "IC6") (pin "20") (pinfunction "AREF_20") (pintype "power_in"))
      (node (ref "IC6") (pin "4") (pinfunction "VCC_4") (pintype "power_in"))
      (node (ref "IC6") (pin "6") (pinfunction "VCC_6") (pintype "power_in"))
      (node (ref "IC7") (pin "19") (pinfunction "~{RESET}_19") (pintype "input"))
      (node (ref "IC7") (pin "20") (pinfunction "VCC_20") (pintype "power_in"))
      (node (ref "IC7") (pin "4") (pinfunction "VCCIO_4") (pintype "power_in"))
      (node (ref "L1") (pin "1") (pinfunction "1_1") (pintype "passive"))
      (node (ref "R16") (pin "1") (pinfunction "P$1_1") (pintype "passive"))
      (node (ref "R17") (pin "2") (pinfunction "P$2_2") (pintype "passive"))
      (node (ref "R22") (pin "2") (pinfunction "P$2_2") (pintype "passive"))
      (node (ref "R28") (pin "2") (pinfunction "P$2_2") (pintype "passive"))
      (node (ref "R29") (pin "2") (pinfunction "P$2_2") (pintype "passive"))
      (node (ref "R7") (pin "2") (pinfunction "P$2_2") (pintype "passive"))
      (node (ref "T1") (pin "2") (pinfunction "S_2") (pintype "passive"))
    )
    (net (code "110") (name "unconnected-(CON1-CEC-Pad13)") (class "Default")
      (node (ref "CON1") (pin "13") (pinfunction "CEC_13") (pintype "bidirectional"))
    )
    (net (code "111") (name "unconnected-(CON1-NC-Pad14)") (class "Default")
      (node (ref "CON1") (pin "14") (pinfunction "NC_14") (pintype "bidirectional"))
    )
    (net (code "112") (name "unconnected-(CON2-NC-Pad35)") (class "Default")
      (node (ref "CON2") (pin "35") (pinfunction "NC_35") (pintype "bidirectional"))
    )
    (net (code "113") (name "unconnected-(CON3-ID-Pad4)") (class "Default")
      (node (ref "CON3") (pin "4") (pinfunction "ID_4") (pintype "bidirectional"))
    )
    (net (code "114") (name "unconnected-(CON4-ID-Pad4)") (class "Default")
      (node (ref "CON4") (pin "4") (pinfunction "ID_4") (pintype "bidirectional"))
    )
    (net (code "115") (name "unconnected-(IC1-CTL1-Pad40)") (class "Default")
      (node (ref "IC1") (pin "40") (pinfunction "CTL1_40") (pintype "bidirectional"))
    )
    (net (code "116") (name "unconnected-(IC1-CTL2-Pad41)") (class "Default")
      (node (ref "IC1") (pin "41") (pinfunction "CTL2_41") (pintype "bidirectional"))
    )
    (net (code "117") (name "unconnected-(IC1-CTL3-Pad42)") (class "Default")
      (node (ref "IC1") (pin "42") (pinfunction "CTL3_42") (pintype "bidirectional"))
    )
    (net (code "118") (name "unconnected-(IC1-EXT_RES-Pad96)") (class "Default")
      (node (ref "IC1") (pin "96") (pinfunction "EXT_RES_96") (pintype "bidirectional"))
    )
    (net (code "119") (name "unconnected-(IC1-QO0-Pad49)") (class "Default")
      (node (ref "IC1") (pin "49") (pinfunction "QO0_49") (pintype "bidirectional"))
    )
    (net (code "120") (name "unconnected-(IC1-QO1-Pad50)") (class "Default")
      (node (ref "IC1") (pin "50") (pinfunction "QO1_50") (pintype "bidirectional"))
    )
    (net (code "121") (name "unconnected-(IC1-QO2-Pad51)") (class "Default")
      (node (ref "IC1") (pin "51") (pinfunction "QO2_51") (pintype "bidirectional"))
    )
    (net (code "122") (name "unconnected-(IC1-QO3-Pad52)") (class "Default")
      (node (ref "IC1") (pin "52") (pinfunction "QO3_52") (pintype "bidirectional"))
    )
    (net (code "123") (name "unconnected-(IC1-QO4-Pad53)") (class "Default")
      (node (ref "IC1") (pin "53") (pinfunction "QO4_53") (pintype "bidirectional"))
    )
    (net (code "124") (name "unconnected-(IC1-QO5-Pad54)") (class "Default")
      (node (ref "IC1") (pin "54") (pinfunction "QO5_54") (pintype "bidirectional"))
    )
    (net (code "125") (name "unconnected-(IC1-QO6-Pad55)") (class "Default")
      (node (ref "IC1") (pin "55") (pinfunction "QO6_55") (pintype "bidirectional"))
    )
    (net (code "126") (name "unconnected-(IC1-QO7-Pad56)") (class "Default")
      (node (ref "IC1") (pin "56") (pinfunction "QO7_56") (pintype "bidirectional"))
    )
    (net (code "127") (name "unconnected-(IC1-QO8-Pad59)") (class "Default")
      (node (ref "IC1") (pin "59") (pinfunction "QO8_59") (pintype "bidirectional"))
    )
    (net (code "128") (name "unconnected-(IC1-QO9-Pad60)") (class "Default")
      (node (ref "IC1") (pin "60") (pinfunction "QO9_60") (pintype "bidirectional"))
    )
    (net (code "129") (name "unconnected-(IC1-QO10-Pad61)") (class "Default")
      (node (ref "IC1") (pin "61") (pinfunction "QO10_61") (pintype "bidirectional"))
    )
    (net (code "130") (name "unconnected-(IC1-QO11-Pad62)") (class "Default")
      (node (ref "IC1") (pin "62") (pinfunction "QO11_62") (pintype "bidirectional"))
    )
    (net (code "131") (name "unconnected-(IC1-QO12-Pad63)") (class "Default")
      (node (ref "IC1") (pin "63") (pinfunction "QO12_63") (pintype "bidirectional"))
    )
    (net (code "132") (name "unconnected-(IC1-QO13-Pad64)") (class "Default")
      (node (ref "IC1") (pin "64") (pinfunction "QO13_64") (pintype "bidirectional"))
    )
    (net (code "133") (name "unconnected-(IC1-QO14-Pad65)") (class "Default")
      (node (ref "IC1") (pin "65") (pinfunction "QO14_65") (pintype "bidirectional"))
    )
    (net (code "134") (name "unconnected-(IC1-QO15-Pad66)") (class "Default")
      (node (ref "IC1") (pin "66") (pinfunction "QO15_66") (pintype "bidirectional"))
    )
    (net (code "135") (name "unconnected-(IC1-QO16-Pad69)") (class "Default")
      (node (ref "IC1") (pin "69") (pinfunction "QO16_69") (pintype "bidirectional"))
    )
    (net (code "136") (name "unconnected-(IC1-QO17-Pad70)") (class "Default")
      (node (ref "IC1") (pin "70") (pinfunction "QO17_70") (pintype "bidirectional"))
    )
    (net (code "137") (name "unconnected-(IC1-QO18-Pad71)") (class "Default")
      (node (ref "IC1") (pin "71") (pinfunction "QO18_71") (pintype "bidirectional"))
    )
    (net (code "138") (name "unconnected-(IC1-QO19-Pad72)") (class "Default")
      (node (ref "IC1") (pin "72") (pinfunction "QO19_72") (pintype "bidirectional"))
    )
    (net (code "139") (name "unconnected-(IC1-QO20-Pad73)") (class "Default")
      (node (ref "IC1") (pin "73") (pinfunction "QO20_73") (pintype "bidirectional"))
    )
    (net (code "140") (name "unconnected-(IC1-QO21-Pad74)") (class "Default")
      (node (ref "IC1") (pin "74") (pinfunction "QO21_74") (pintype "bidirectional"))
    )
    (net (code "141") (name "unconnected-(IC1-QO22-Pad75)") (class "Default")
      (node (ref "IC1") (pin "75") (pinfunction "QO22_75") (pintype "bidirectional"))
    )
    (net (code "142") (name "unconnected-(IC1-QO23-Pad77)") (class "Default")
      (node (ref "IC1") (pin "77") (pinfunction "QO23_77") (pintype "bidirectional"))
    )
    (net (code "143") (name "unconnected-(IC1-~{PDO}-Pad9)") (class "Default")
      (node (ref "IC1") (pin "9") (pinfunction "~{PDO}_9") (pintype "bidirectional"))
    )
    (net (code "144") (name "unconnected-(IC1-~{PD}-Pad2)") (class "Default")
      (node (ref "IC1") (pin "2") (pinfunction "~{PD}_2") (pintype "bidirectional"))
    )
    (net (code "145") (name "unconnected-(IC5-MODE-Pad4)") (class "Default")
      (node (ref "IC5") (pin "4") (pinfunction "MODE_4") (pintype "passive"))
    )
    (net (code "146") (name "unconnected-(IC5-UART_RX-Pad12)") (class "Default")
      (node (ref "IC5") (pin "12") (pinfunction "UART_RX_12") (pintype "passive"))
    )
    (net (code "147") (name "unconnected-(IC5-UART_TX-Pad10)") (class "Default")
      (node (ref "IC5") (pin "10") (pinfunction "UART_TX_10") (pintype "passive"))
    )
    (net (code "148") (name "unconnected-(IC6-(PCINT18{slash}INT0)PD2-Pad32)") (class "Default")
      (node (ref "IC6") (pin "32") (pinfunction "(PCINT18/INT0)PD2_32") (pintype "bidirectional"))
    )
    (net (code "149") (name "unconnected-(IC6-(PCINT19{slash}OC2B{slash}INT1)PD3-Pad1)") (class "Default")
      (node (ref "IC6") (pin "1") (pinfunction "(PCINT19/OC2B/INT1)PD3_1") (pintype "bidirectional"))
    )
    (net (code "150") (name "unconnected-(IC6-(PCINT20{slash}XCK{slash}T0)PD4-Pad2)") (class "Default")
      (node (ref "IC6") (pin "2") (pinfunction "(PCINT20/XCK/T0)PD4_2") (pintype "bidirectional"))
    )
    (net (code "151") (name "unconnected-(IC6-(PCINT21{slash}OC0B{slash}T1)PD5-Pad9)") (class "Default")
      (node (ref "IC6") (pin "9") (pinfunction "(PCINT21/OC0B/T1)PD5_9") (pintype "bidirectional"))
    )
    (net (code "152") (name "unconnected-(IC6-(PCINT22{slash}OC0A{slash}AIN0)PD6-Pad10)") (class "Default")
      (node (ref "IC6") (pin "10") (pinfunction "(PCINT22/OC0A/AIN0)PD6_10") (pintype "bidirectional"))
    )
    (net (code "153") (name "unconnected-(IC6-(PCINT23{slash}AIN1)PD7-Pad11)") (class "Default")
      (node (ref "IC6") (pin "11") (pinfunction "(PCINT23/AIN1)PD7_11") (pintype "bidirectional"))
    )
    (net (code "154") (name "unconnected-(IC6-ADC6-Pad19)") (class "Default")
      (node (ref "IC6") (pin "19") (pinfunction "ADC6_19") (pintype "bidirectional"))
    )
    (net (code "155") (name "unconnected-(IC6-ADC7-Pad22)") (class "Default")
      (node (ref "IC6") (pin "22") (pinfunction "ADC7_22") (pintype "bidirectional"))
    )
    (net (code "156") (name "unconnected-(IC6-PB0(PCINT0{slash}CLKO{slash}ICP1)-Pad12)") (class "Default")
      (node (ref "IC6") (pin "12") (pinfunction "PB0(PCINT0/CLKO/ICP1)_12") (pintype "bidirectional"))
    )
    (net (code "157") (name "unconnected-(IC6-PB1(OC1A{slash}PCINT1)-Pad13)") (class "Default")
      (node (ref "IC6") (pin "13") (pinfunction "PB1(OC1A/PCINT1)_13") (pintype "bidirectional"))
    )
    (net (code "158") (name "unconnected-(IC6-PB2(SS{slash}OC1B{slash}PCINT2)-Pad14)") (class "Default")
      (node (ref "IC6") (pin "14") (pinfunction "PB2(SS/OC1B/PCINT2)_14") (pintype "bidirectional"))
    )
    (net (code "159") (name "unconnected-(IC6-PC0(ADC0{slash}PCINT8)-Pad23)") (class "Default")
      (node (ref "IC6") (pin "23") (pinfunction "PC0(ADC0/PCINT8)_23") (pintype "bidirectional"))
    )
    (net (code "160") (name "unconnected-(IC6-PC1(ADC1{slash}PCINT9)-Pad24)") (class "Default")
      (node (ref "IC6") (pin "24") (pinfunction "PC1(ADC1/PCINT9)_24") (pintype "bidirectional"))
    )
    (net (code "161") (name "unconnected-(IC6-PC2(ADC2{slash}PCINT10)-Pad25)") (class "Default")
      (node (ref "IC6") (pin "25") (pinfunction "PC2(ADC2/PCINT10)_25") (pintype "bidirectional"))
    )
    (net (code "162") (name "unconnected-(IC6-PC3(ADC3{slash}PCINT11)-Pad26)") (class "Default")
      (node (ref "IC6") (pin "26") (pinfunction "PC3(ADC3/PCINT11)_26") (pintype "bidirectional"))
    )
    (net (code "163") (name "unconnected-(IC7-CBUS0-Pad23)") (class "Default")
      (node (ref "IC7") (pin "23") (pinfunction "CBUS0_23") (pintype "bidirectional"))
    )
    (net (code "164") (name "unconnected-(IC7-CBUS1-Pad22)") (class "Default")
      (node (ref "IC7") (pin "22") (pinfunction "CBUS1_22") (pintype "bidirectional"))
    )
    (net (code "165") (name "unconnected-(IC7-CBUS2-Pad13)") (class "Default")
      (node (ref "IC7") (pin "13") (pinfunction "CBUS2_13") (pintype "bidirectional"))
    )
    (net (code "166") (name "unconnected-(IC7-CBUS3-Pad14)") (class "Default")
      (node (ref "IC7") (pin "14") (pinfunction "CBUS3_14") (pintype "bidirectional"))
    )
    (net (code "167") (name "unconnected-(IC7-CBUS4-Pad12)") (class "Default")
      (node (ref "IC7") (pin "12") (pinfunction "CBUS4_12") (pintype "bidirectional"))
    )
    (net (code "168") (name "unconnected-(IC7-OSCI-Pad27)") (class "Default")
      (node (ref "IC7") (pin "27") (pinfunction "OSCI_27") (pintype "input"))
    )
    (net (code "169") (name "unconnected-(IC7-OSCO-Pad28)") (class "Default")
      (node (ref "IC7") (pin "28") (pinfunction "OSCO_28") (pintype "output"))
    )
    (net (code "170") (name "unconnected-(IC7-~{CTS}-Pad11)") (class "Default")
      (node (ref "IC7") (pin "11") (pinfunction "~{CTS}_11") (pintype "input"))
    )
    (net (code "171") (name "unconnected-(IC7-~{DCD}-Pad10)") (class "Default")
      (node (ref "IC7") (pin "10") (pinfunction "~{DCD}_10") (pintype "input"))
    )
    (net (code "172") (name "unconnected-(IC7-~{DSR}-Pad9)") (class "Default")
      (node (ref "IC7") (pin "9") (pinfunction "~{DSR}_9") (pintype "input"))
    )
    (net (code "173") (name "unconnected-(IC7-~{DTR}-Pad2)") (class "Default")
      (node (ref "IC7") (pin "2") (pinfunction "~{DTR}_2") (pintype "output"))
    )
    (net (code "174") (name "unconnected-(IC7-~{RI}-Pad6)") (class "Default")
      (node (ref "IC7") (pin "6") (pinfunction "~{RI}_6") (pintype "input"))
    )
    (net (code "175") (name "unconnected-(IC7-~{RTS}-Pad3)") (class "Default")
      (node (ref "IC7") (pin "3") (pinfunction "~{RTS}_3") (pintype "output"))
    )
  )
)
